# interfacez.net
KiCad netlist of a schematic drawn in EAGLE
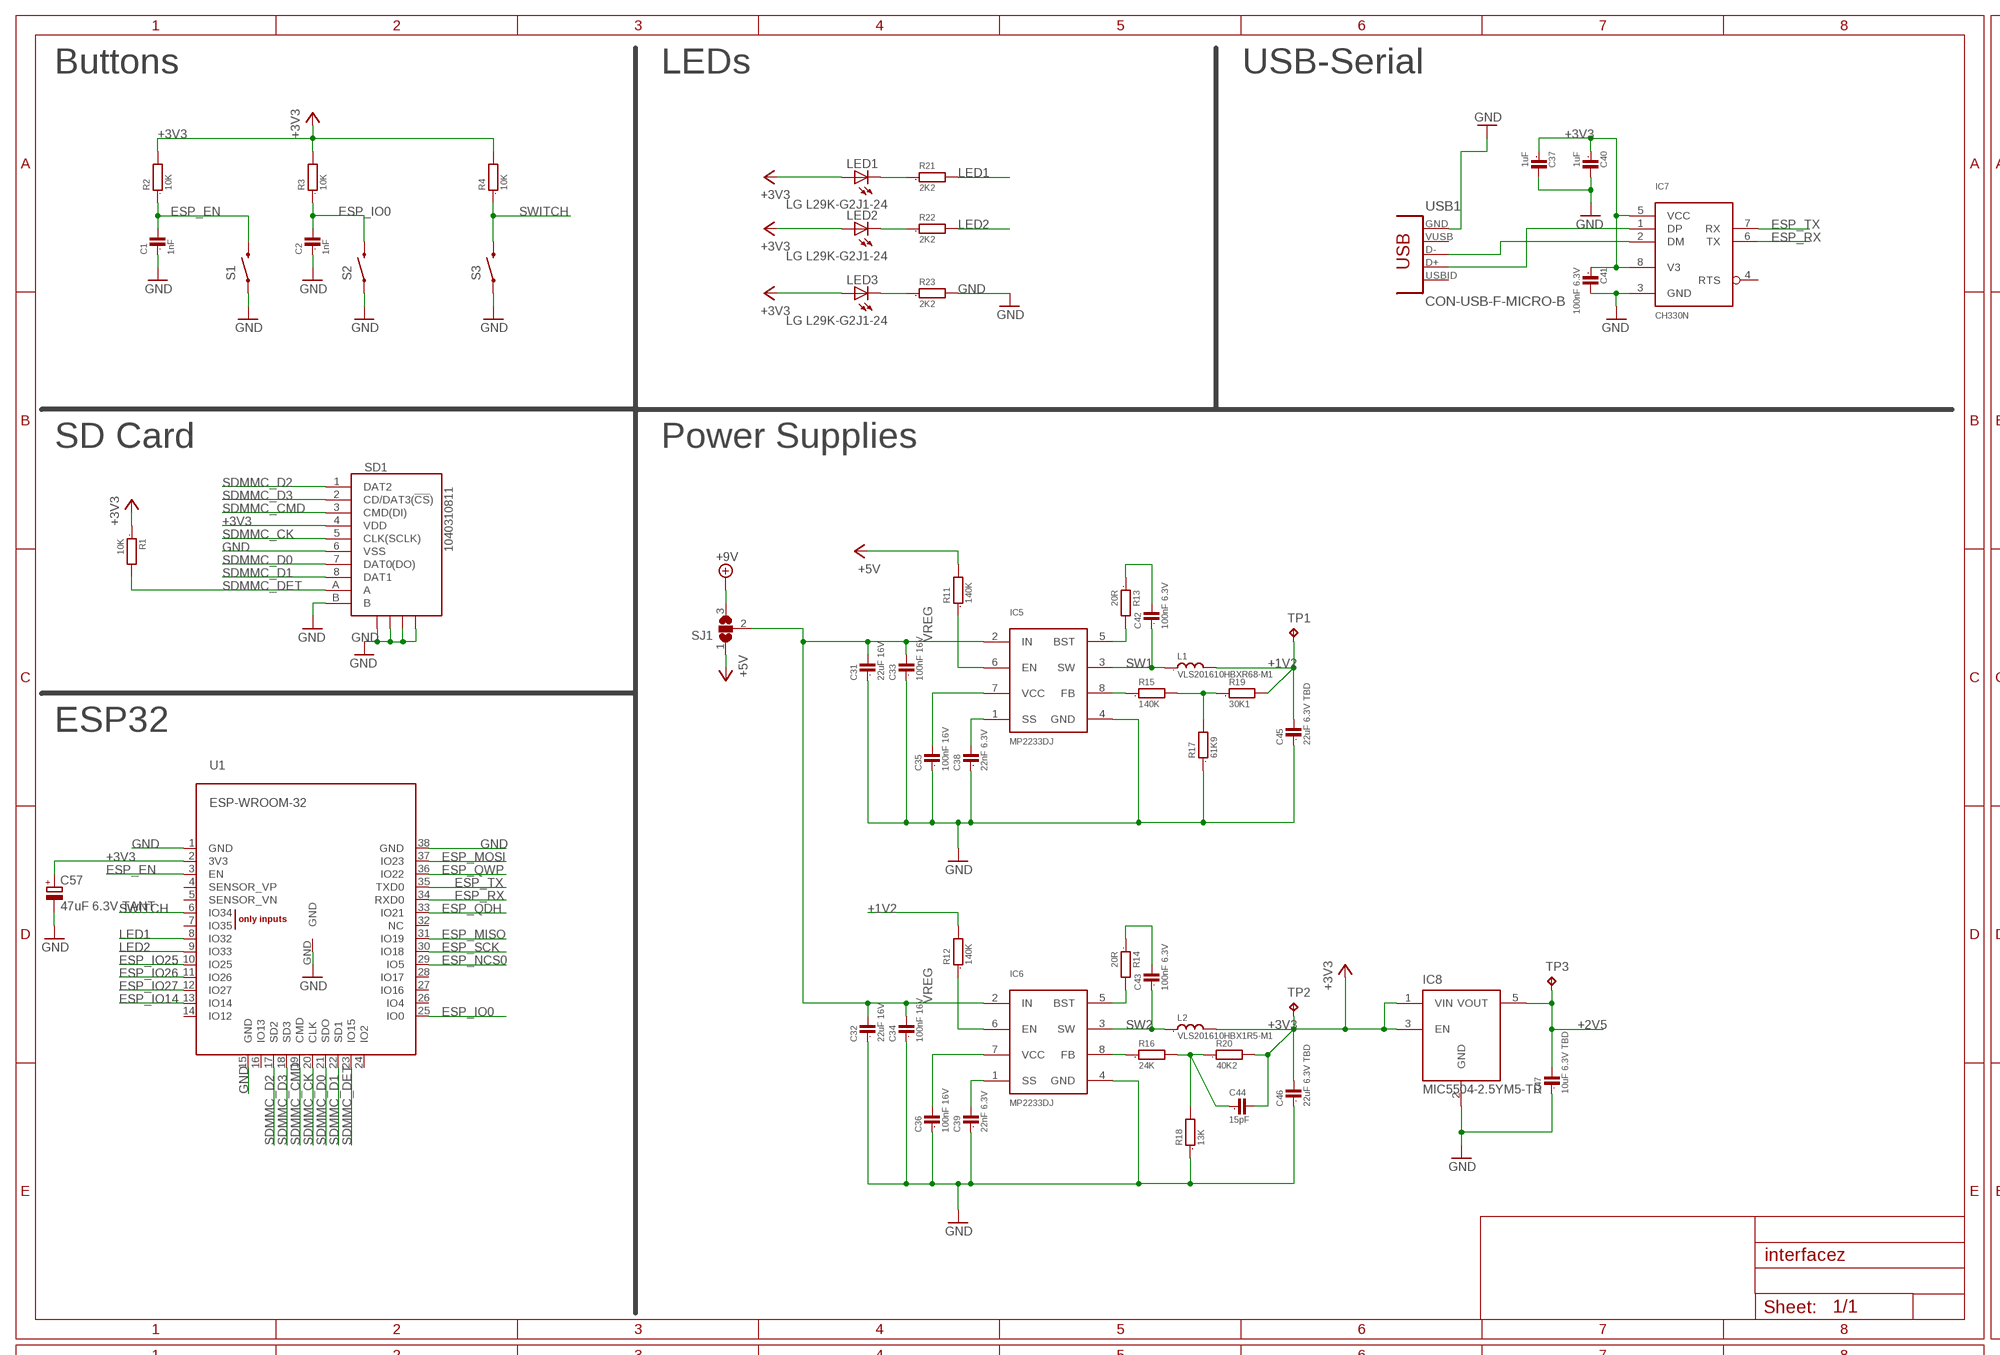
[diagram p0: schematic, sheet 1, part 1 of 3]
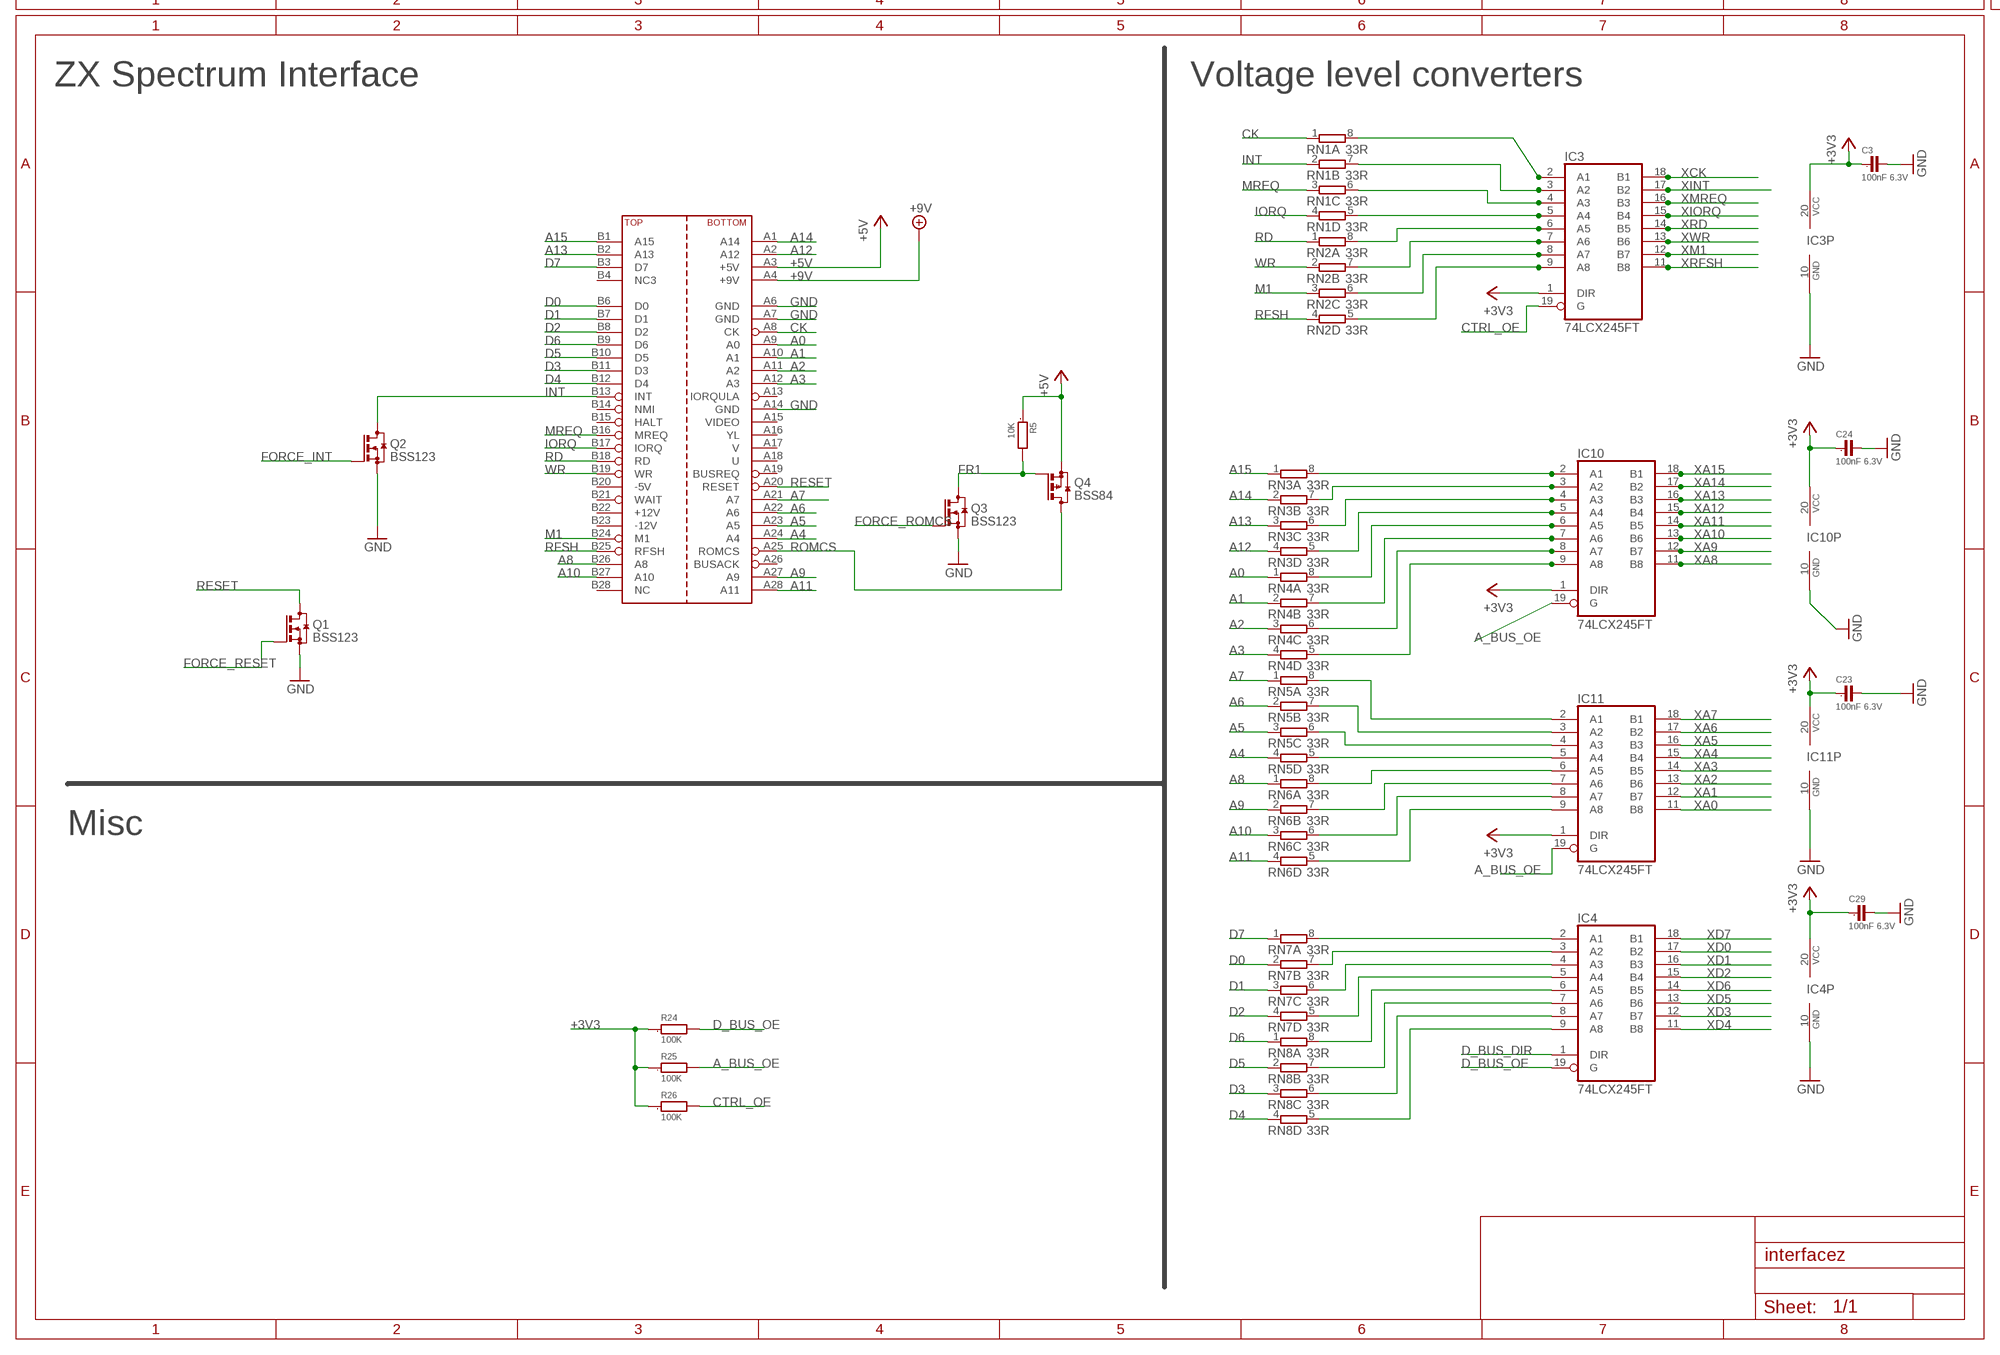
[diagram p1: schematic, sheet 1, part 2 of 3]
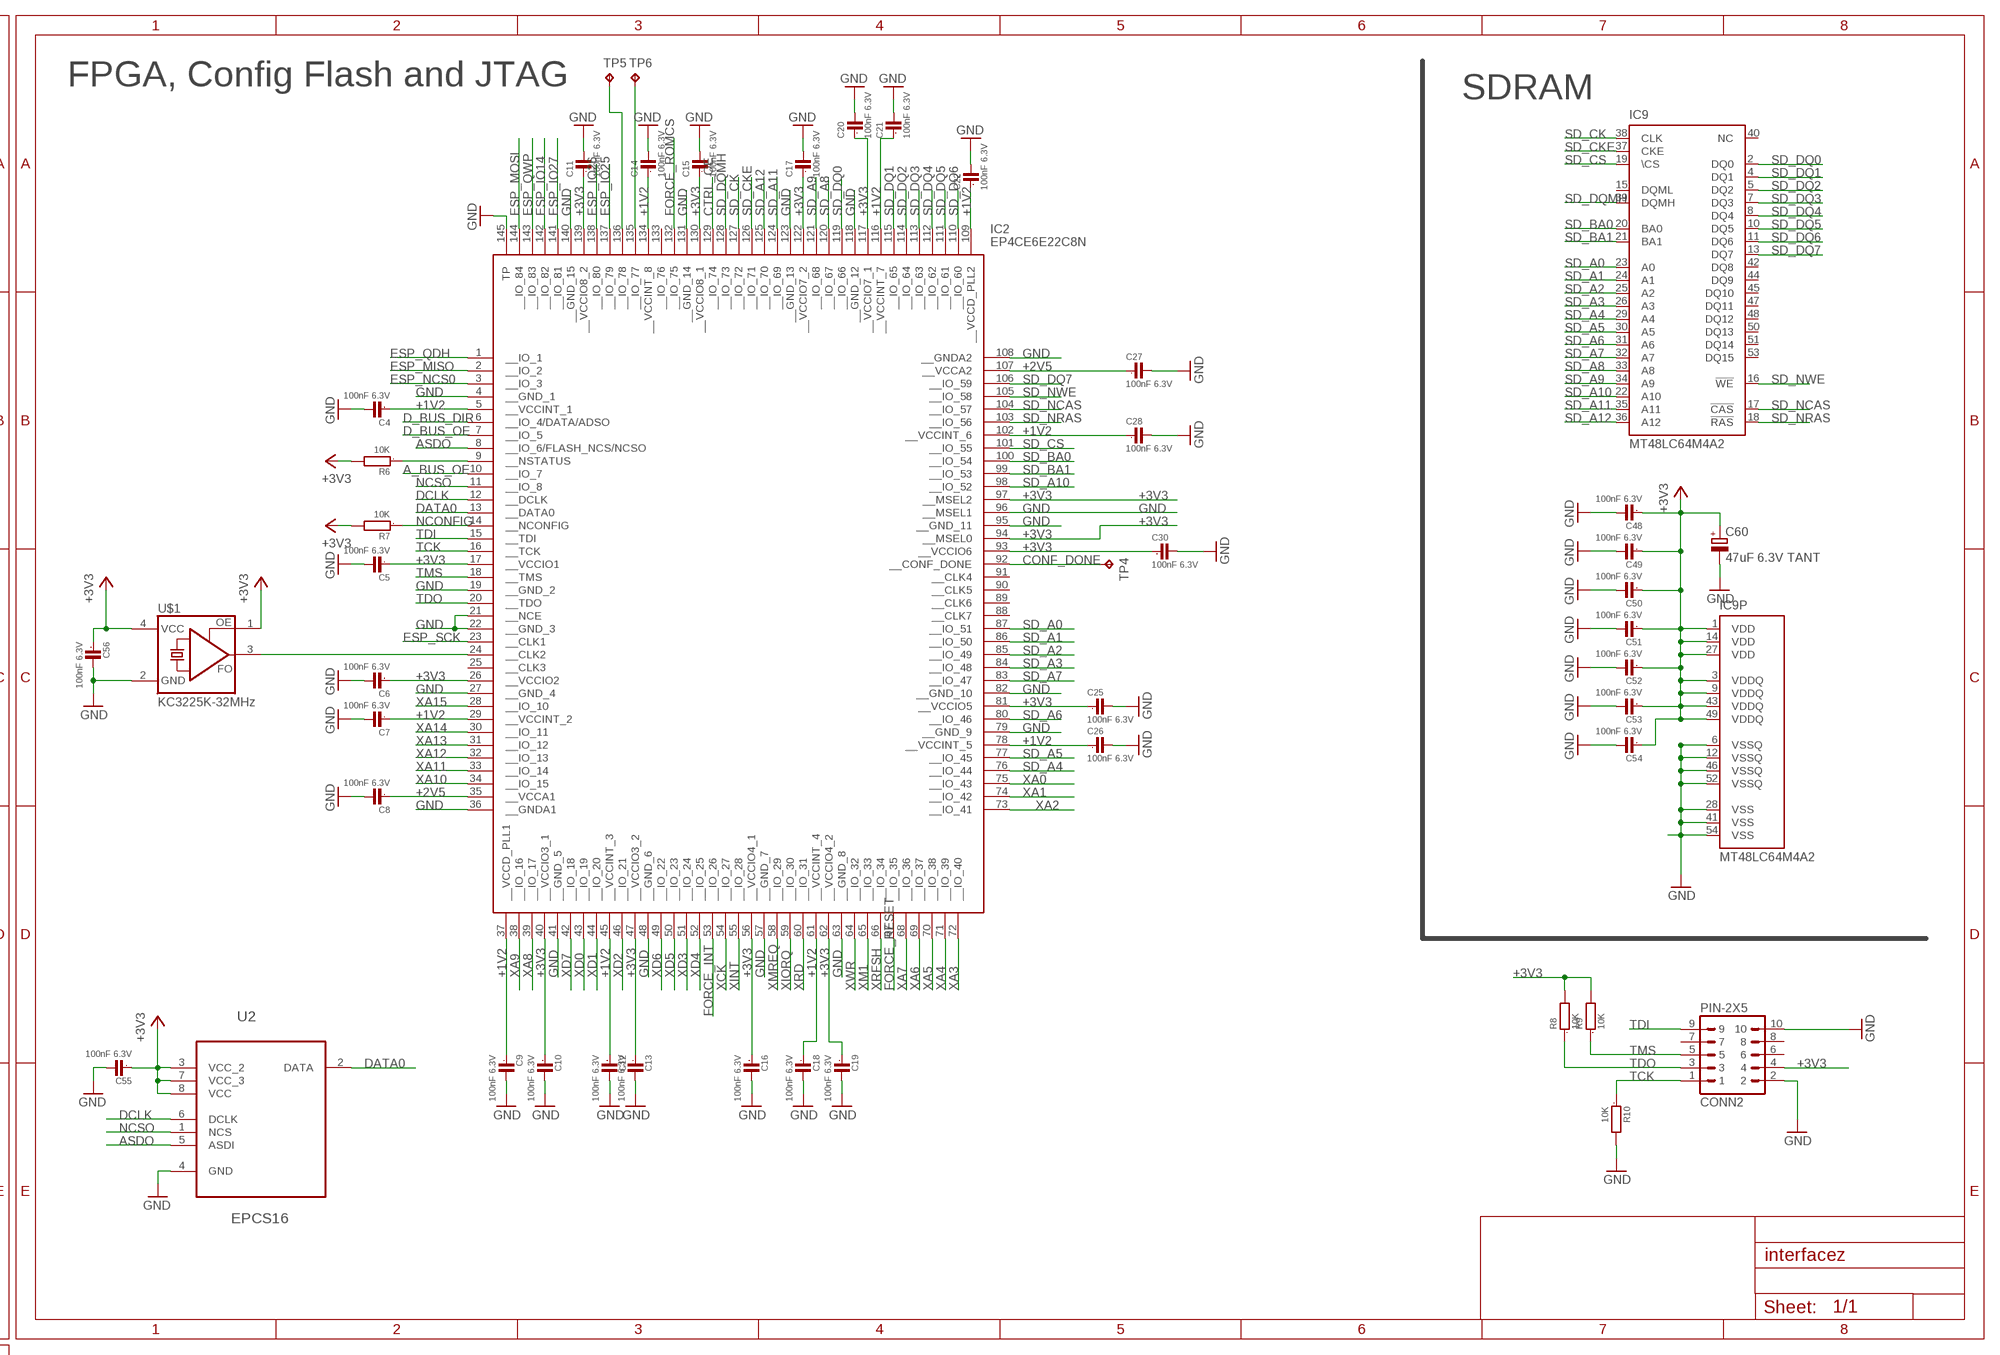
[diagram p2: schematic, sheet 1, part 3 of 3]

(export (version "E")
  (design (tool "Eeschema 10.0.6"))
  (components
    (comp (ref "C1")
      (value "1nF")
      (footprint "eagle-import:0603")
      (libsource (lib "eagle-import") (part "C0603"))
    )
    (comp (ref "C2")
      (value "1nF")
      (footprint "eagle-import:0603")
      (libsource (lib "eagle-import") (part "C0603"))
    )
    (comp (ref "C3")
      (value "100nF 6.3V")
      (footprint "eagle-import:0603")
      (libsource (lib "eagle-import") (part "C0603"))
    )
    (comp (ref "C4")
      (value "100nF 6.3V")
      (footprint "eagle-import:0603")
      (libsource (lib "eagle-import") (part "C0603"))
    )
    (comp (ref "C5")
      (value "100nF 6.3V")
      (footprint "eagle-import:0603")
      (libsource (lib "eagle-import") (part "C0603"))
    )
    (comp (ref "C6")
      (value "100nF 6.3V")
      (footprint "eagle-import:0603")
      (libsource (lib "eagle-import") (part "C0603"))
    )
    (comp (ref "C7")
      (value "100nF 6.3V")
      (footprint "eagle-import:0603")
      (libsource (lib "eagle-import") (part "C0603"))
    )
    (comp (ref "C8")
      (value "100nF 6.3V")
      (footprint "eagle-import:0603")
      (libsource (lib "eagle-import") (part "C0603"))
    )
    (comp (ref "C9")
      (value "100nF 6.3V")
      (footprint "eagle-import:0603")
      (libsource (lib "eagle-import") (part "C0603"))
    )
    (comp (ref "C10")
      (value "100nF 6.3V")
      (footprint "eagle-import:0603")
      (libsource (lib "eagle-import") (part "C0603"))
    )
    (comp (ref "C11")
      (value "100nF 6.3V")
      (footprint "eagle-import:0603")
      (libsource (lib "eagle-import") (part "C0603"))
    )
    (comp (ref "C12")
      (value "100nF 6.3V")
      (footprint "eagle-import:0603")
      (libsource (lib "eagle-import") (part "C0603"))
    )
    (comp (ref "C13")
      (value "100nF 6.3V")
      (footprint "eagle-import:0603")
      (libsource (lib "eagle-import") (part "C0603"))
    )
    (comp (ref "C14")
      (value "100nF 6.3V")
      (footprint "eagle-import:0603")
      (libsource (lib "eagle-import") (part "C0603"))
    )
    (comp (ref "C15")
      (value "100nF 6.3V")
      (footprint "eagle-import:0603")
      (libsource (lib "eagle-import") (part "C0603"))
    )
    (comp (ref "C16")
      (value "100nF 6.3V")
      (footprint "eagle-import:0603")
      (libsource (lib "eagle-import") (part "C0603"))
    )
    (comp (ref "C17")
      (value "100nF 6.3V")
      (footprint "eagle-import:0603")
      (libsource (lib "eagle-import") (part "C0603"))
    )
    (comp (ref "C18")
      (value "100nF 6.3V")
      (footprint "eagle-import:0603")
      (libsource (lib "eagle-import") (part "C0603"))
    )
    (comp (ref "C19")
      (value "100nF 6.3V")
      (footprint "eagle-import:0603")
      (libsource (lib "eagle-import") (part "C0603"))
    )
    (comp (ref "C20")
      (value "100nF 6.3V")
      (footprint "eagle-import:0603")
      (libsource (lib "eagle-import") (part "C0603"))
    )
    (comp (ref "C21")
      (value "100nF 6.3V")
      (footprint "eagle-import:0603")
      (libsource (lib "eagle-import") (part "C0603"))
    )
    (comp (ref "C22")
      (value "100nF 6.3V")
      (footprint "eagle-import:0603")
      (libsource (lib "eagle-import") (part "C0603"))
    )
    (comp (ref "C23")
      (value "100nF 6.3V")
      (footprint "eagle-import:0603")
      (libsource (lib "eagle-import") (part "C0603"))
    )
    (comp (ref "C24")
      (value "100nF 6.3V")
      (footprint "eagle-import:0603")
      (libsource (lib "eagle-import") (part "C0603"))
    )
    (comp (ref "C25")
      (value "100nF 6.3V")
      (footprint "eagle-import:0603")
      (libsource (lib "eagle-import") (part "C0603"))
    )
    (comp (ref "C26")
      (value "100nF 6.3V")
      (footprint "eagle-import:0603")
      (libsource (lib "eagle-import") (part "C0603"))
    )
    (comp (ref "C27")
      (value "100nF 6.3V")
      (footprint "eagle-import:0603")
      (libsource (lib "eagle-import") (part "C0603"))
    )
    (comp (ref "C28")
      (value "100nF 6.3V")
      (footprint "eagle-import:0603")
      (libsource (lib "eagle-import") (part "C0603"))
    )
    (comp (ref "C29")
      (value "100nF 6.3V")
      (footprint "eagle-import:0603")
      (libsource (lib "eagle-import") (part "C0603"))
    )
    (comp (ref "C30")
      (value "100nF 6.3V")
      (footprint "eagle-import:0603")
      (libsource (lib "eagle-import") (part "C0603"))
    )
    (comp (ref "C31")
      (value "22uF 16V")
      (footprint "eagle-import:1210")
      (libsource (lib "eagle-import") (part "C1210"))
    )
    (comp (ref "C32")
      (value "22uF 16V")
      (footprint "eagle-import:1210")
      (libsource (lib "eagle-import") (part "C1210"))
    )
    (comp (ref "C33")
      (value "100nF 16V")
      (footprint "eagle-import:0603")
      (libsource (lib "eagle-import") (part "C0603"))
    )
    (comp (ref "C34")
      (value "100nF 16V")
      (footprint "eagle-import:0603")
      (libsource (lib "eagle-import") (part "C0603"))
    )
    (comp (ref "C35")
      (value "100nF 16V")
      (footprint "eagle-import:0603")
      (libsource (lib "eagle-import") (part "C0603"))
    )
    (comp (ref "C36")
      (value "100nF 16V")
      (footprint "eagle-import:0603")
      (libsource (lib "eagle-import") (part "C0603"))
    )
    (comp (ref "C37")
      (value "1uF")
      (footprint "eagle-import:0603")
      (libsource (lib "eagle-import") (part "C0603"))
    )
    (comp (ref "C38")
      (value "22nF 6.3V")
      (footprint "eagle-import:0603")
      (libsource (lib "eagle-import") (part "C0603"))
    )
    (comp (ref "C39")
      (value "22nF 6.3V")
      (footprint "eagle-import:0603")
      (libsource (lib "eagle-import") (part "C0603"))
    )
    (comp (ref "C40")
      (value "1uF")
      (footprint "eagle-import:0603")
      (libsource (lib "eagle-import") (part "C0603"))
    )
    (comp (ref "C41")
      (value "100nF 6.3V")
      (footprint "eagle-import:0603")
      (libsource (lib "eagle-import") (part "C0603"))
    )
    (comp (ref "C42")
      (value "100nF 6.3V")
      (footprint "eagle-import:0603")
      (libsource (lib "eagle-import") (part "C0603"))
    )
    (comp (ref "C43")
      (value "100nF 6.3V")
      (footprint "eagle-import:0603")
      (libsource (lib "eagle-import") (part "C0603"))
    )
    (comp (ref "C44")
      (value "15pF")
      (footprint "eagle-import:0603")
      (libsource (lib "eagle-import") (part "C0603"))
    )
    (comp (ref "C45")
      (value "22uF 6.3V TBD")
      (footprint "eagle-import:0805")
      (libsource (lib "eagle-import") (part "C0805"))
    )
    (comp (ref "C46")
      (value "22uF 6.3V TBD")
      (footprint "eagle-import:0805")
      (libsource (lib "eagle-import") (part "C0805"))
    )
    (comp (ref "C47")
      (value "10uF 6.3V TBD")
      (footprint "eagle-import:0805")
      (libsource (lib "eagle-import") (part "C0805"))
    )
    (comp (ref "C48")
      (value "100nF 6.3V")
      (footprint "eagle-import:0603")
      (libsource (lib "eagle-import") (part "C0603"))
    )
    (comp (ref "C49")
      (value "100nF 6.3V")
      (footprint "eagle-import:0603")
      (libsource (lib "eagle-import") (part "C0603"))
    )
    (comp (ref "C50")
      (value "100nF 6.3V")
      (footprint "eagle-import:0603")
      (libsource (lib "eagle-import") (part "C0603"))
    )
    (comp (ref "C51")
      (value "100nF 6.3V")
      (footprint "eagle-import:0603")
      (libsource (lib "eagle-import") (part "C0603"))
    )
    (comp (ref "C52")
      (value "100nF 6.3V")
      (footprint "eagle-import:0603")
      (libsource (lib "eagle-import") (part "C0603"))
    )
    (comp (ref "C53")
      (value "100nF 6.3V")
      (footprint "eagle-import:0603")
      (libsource (lib "eagle-import") (part "C0603"))
    )
    (comp (ref "C54")
      (value "100nF 6.3V")
      (footprint "eagle-import:0603")
      (libsource (lib "eagle-import") (part "C0603"))
    )
    (comp (ref "C55")
      (value "100nF 6.3V")
      (footprint "eagle-import:0603")
      (libsource (lib "eagle-import") (part "C0603"))
    )
    (comp (ref "C56")
      (value "100nF 6.3V")
      (footprint "eagle-import:0603")
      (libsource (lib "eagle-import") (part "C0603"))
    )
    (comp (ref "C57")
      (value "47uF 6.3V TANT")
      (footprint "eagle-import:TANT_CASE_A")
      (libsource (lib "eagle-import") (part "TANT_CASE_A"))
    )
    (comp (ref "C60")
      (value "47uF 6.3V TANT")
      (footprint "eagle-import:TANT_CASE_A")
      (libsource (lib "eagle-import") (part "TANT_CASE_A"))
    )
    (comp (ref "CONN1")
      (value "ZX_EDGE_DAUGHTERBOARD")
      (footprint "eagle-import:ZX-EDGE-DAUGHTERBOARD")
      (libsource (lib "eagle-import") (part "ZX_EDGE_DAUGHTERBOARD"))
    )
    (comp (ref "CONN2")
      (value "PIN-2X5")
      (footprint "eagle-import:PIN-2X5")
      (libsource (lib "eagle-import") (part "PIN-2X5"))
    )
    (comp (ref "IC2")
      (value "EP4CE6E22C8N")
      (footprint "eagle-import:QFP50P2200X2200X165-145N")
      (fields (field (name "MOUSER_PART_NUMBER") "989-EP4CE6E22C8N"))
      (libsource (lib "eagle-import") (part "EP4CE6E22C8N"))
    )
    (comp (ref "IC3")
      (value "74LCX245FT")
      (footprint "eagle-import:TSSOP20")
      (libsource (lib "eagle-import") (part "74245"))
    )
    (comp (ref "IC4")
      (value "74LCX245FT")
      (footprint "eagle-import:TSSOP20")
      (libsource (lib "eagle-import") (part "74245"))
    )
    (comp (ref "IC5")
      (value "MP2233DJ")
      (footprint "eagle-import:SOT23-8L")
      (libsource (lib "eagle-import") (part "MP2233DJ"))
    )
    (comp (ref "IC6")
      (value "MP2233DJ")
      (footprint "eagle-import:SOT23-8L")
      (libsource (lib "eagle-import") (part "MP2233DJ"))
    )
    (comp (ref "IC7")
      (value "CH330N")
      (footprint "eagle-import:SOIC8")
      (libsource (lib "eagle-import") (part "CH330N"))
    )
    (comp (ref "IC8")
      (value "MIC5504-2.5YM5-TR")
      (footprint "eagle-import:SOT23-5L")
      (libsource (lib "eagle-import") (part "MIC550X"))
    )
    (comp (ref "IC9")
      (value "MT48LC64M4A2")
      (footprint "eagle-import:TSOP54-400")
      (libsource (lib "eagle-import") (part "MT48LC64M4A2"))
    )
    (comp (ref "IC10")
      (value "74LCX245FT")
      (footprint "eagle-import:TSSOP20")
      (libsource (lib "eagle-import") (part "74245"))
    )
    (comp (ref "IC11")
      (value "74LCX245FT")
      (footprint "eagle-import:TSSOP20")
      (libsource (lib "eagle-import") (part "74245"))
    )
    (comp (ref "L1")
      (value "VLS201610HBXR68-M1")
      (footprint "eagle-import:IND_0806")
      (libsource (lib "eagle-import") (part "VLS201610HBXR68-M1"))
    )
    (comp (ref "L2")
      (value "VLS201610HBX1R5-M1")
      (footprint "eagle-import:IND_0806")
      (libsource (lib "eagle-import") (part "VLS201610HBX1R5-M1"))
    )
    (comp (ref "LED1")
      (value "LG L29K-G2J1-24")
      (footprint "eagle-import:LED-603")
      (libsource (lib "eagle-import") (part "LED-0603"))
    )
    (comp (ref "LED2")
      (value "LG L29K-G2J1-24")
      (footprint "eagle-import:LED-603")
      (libsource (lib "eagle-import") (part "LED-0603"))
    )
    (comp (ref "LED3")
      (value "LG L29K-G2J1-24")
      (footprint "eagle-import:LED-603")
      (libsource (lib "eagle-import") (part "LED-0603"))
    )
    (comp (ref "Q1")
      (value "BSS123")
      (footprint "eagle-import:SOT23")
      (libsource (lib "eagle-import") (part "BSS123"))
    )
    (comp (ref "Q2")
      (value "BSS123")
      (footprint "eagle-import:SOT23")
      (libsource (lib "eagle-import") (part "BSS123"))
    )
    (comp (ref "Q3")
      (value "BSS123")
      (footprint "eagle-import:SOT23")
      (libsource (lib "eagle-import") (part "BSS123"))
    )
    (comp (ref "Q4")
      (value "BSS84")
      (footprint "eagle-import:SOT23")
      (libsource (lib "eagle-import") (part "BSS84"))
    )
    (comp (ref "R1")
      (value "10K")
      (footprint "eagle-import:0603")
      (libsource (lib "eagle-import") (part "R0603"))
    )
    (comp (ref "R2")
      (value "10K")
      (footprint "eagle-import:0603")
      (libsource (lib "eagle-import") (part "R0603"))
    )
    (comp (ref "R3")
      (value "10K")
      (footprint "eagle-import:0603")
      (libsource (lib "eagle-import") (part "R0603"))
    )
    (comp (ref "R4")
      (value "10K")
      (footprint "eagle-import:0603")
      (libsource (lib "eagle-import") (part "R0603"))
    )
    (comp (ref "R5")
      (value "10K")
      (footprint "eagle-import:0603")
      (libsource (lib "eagle-import") (part "R0603"))
    )
    (comp (ref "R6")
      (value "10K")
      (footprint "eagle-import:0603")
      (libsource (lib "eagle-import") (part "R0603"))
    )
    (comp (ref "R7")
      (value "10K")
      (footprint "eagle-import:0603")
      (libsource (lib "eagle-import") (part "R0603"))
    )
    (comp (ref "R8")
      (value "10K")
      (footprint "eagle-import:0603")
      (libsource (lib "eagle-import") (part "R0603"))
    )
    (comp (ref "R9")
      (value "10K")
      (footprint "eagle-import:0603")
      (libsource (lib "eagle-import") (part "R0603"))
    )
    (comp (ref "R10")
      (value "10K")
      (footprint "eagle-import:0603")
      (libsource (lib "eagle-import") (part "R0603"))
    )
    (comp (ref "R11")
      (value "140K")
      (footprint "eagle-import:0603")
      (libsource (lib "eagle-import") (part "R0603"))
    )
    (comp (ref "R12")
      (value "140K")
      (footprint "eagle-import:0603")
      (libsource (lib "eagle-import") (part "R0603"))
    )
    (comp (ref "R13")
      (value "20R")
      (footprint "eagle-import:0603")
      (libsource (lib "eagle-import") (part "R0603"))
    )
    (comp (ref "R14")
      (value "20R")
      (footprint "eagle-import:0603")
      (libsource (lib "eagle-import") (part "R0603"))
    )
    (comp (ref "R15")
      (value "140K")
      (footprint "eagle-import:0603")
      (libsource (lib "eagle-import") (part "R0603"))
    )
    (comp (ref "R16")
      (value "24K")
      (footprint "eagle-import:0603")
      (libsource (lib "eagle-import") (part "R0603"))
    )
    (comp (ref "R17")
      (value "61K9")
      (footprint "eagle-import:0603")
      (libsource (lib "eagle-import") (part "R0603"))
    )
    (comp (ref "R18")
      (value "13K")
      (footprint "eagle-import:0603")
      (libsource (lib "eagle-import") (part "R0603"))
    )
    (comp (ref "R19")
      (value "30K1")
      (footprint "eagle-import:0603")
      (libsource (lib "eagle-import") (part "R0603"))
    )
    (comp (ref "R20")
      (value "40K2")
      (footprint "eagle-import:0603")
      (libsource (lib "eagle-import") (part "R0603"))
    )
    (comp (ref "R21")
      (value "2K2")
      (footprint "eagle-import:0603")
      (libsource (lib "eagle-import") (part "R0603"))
    )
    (comp (ref "R22")
      (value "2K2")
      (footprint "eagle-import:0603")
      (libsource (lib "eagle-import") (part "R0603"))
    )
    (comp (ref "R23")
      (value "2K2")
      (footprint "eagle-import:0603")
      (libsource (lib "eagle-import") (part "R0603"))
    )
    (comp (ref "R24")
      (value "100K")
      (footprint "eagle-import:0603")
      (libsource (lib "eagle-import") (part "R0603"))
    )
    (comp (ref "R25")
      (value "100K")
      (footprint "eagle-import:0603")
      (libsource (lib "eagle-import") (part "R0603"))
    )
    (comp (ref "R26")
      (value "100K")
      (footprint "eagle-import:0603")
      (libsource (lib "eagle-import") (part "R0603"))
    )
    (comp (ref "RN1")
      (value "33R")
      (footprint "eagle-import:EXB28V")
      (libsource (lib "eagle-import") (part "4R-NEXB28V"))
    )
    (comp (ref "RN2")
      (value "33R")
      (footprint "eagle-import:EXB28V")
      (libsource (lib "eagle-import") (part "4R-NEXB28V"))
    )
    (comp (ref "RN3")
      (value "33R")
      (footprint "eagle-import:EXB28V")
      (libsource (lib "eagle-import") (part "4R-NEXB28V"))
    )
    (comp (ref "RN4")
      (value "33R")
      (footprint "eagle-import:EXB28V")
      (libsource (lib "eagle-import") (part "4R-NEXB28V"))
    )
    (comp (ref "RN5")
      (value "33R")
      (footprint "eagle-import:EXB28V")
      (libsource (lib "eagle-import") (part "4R-NEXB28V"))
    )
    (comp (ref "RN6")
      (value "33R")
      (footprint "eagle-import:EXB28V")
      (libsource (lib "eagle-import") (part "4R-NEXB28V"))
    )
    (comp (ref "RN7")
      (value "33R")
      (footprint "eagle-import:EXB28V")
      (libsource (lib "eagle-import") (part "4R-NEXB28V"))
    )
    (comp (ref "RN8")
      (value "33R")
      (footprint "eagle-import:EXB28V")
      (libsource (lib "eagle-import") (part "4R-NEXB28V"))
    )
    (comp (ref "S1")
      (value "SWITCHES_SMD-4")
      (footprint "eagle-import:TACTILE_SWITCH_TALL")
      (libsource (lib "eagle-import") (part "SWITCHES_SMD-4"))
    )
    (comp (ref "S2")
      (value "SWITCHES_SMD-4")
      (footprint "eagle-import:TACTILE_SWITCH_TALL")
      (libsource (lib "eagle-import") (part "SWITCHES_SMD-4"))
    )
    (comp (ref "S3")
      (value "SWITCHES_SMD-4")
      (footprint "eagle-import:TACTILE_SWITCH_TALL")
      (libsource (lib "eagle-import") (part "SWITCHES_SMD-4"))
    )
    (comp (ref "SD1")
      (value "1040310811")
      (footprint "eagle-import:1040310811")
      (libsource (lib "eagle-import") (part "1040310811"))
    )
    (comp (ref "SJ1")
      (value "SJ2W")
      (footprint "eagle-import:SJ_2")
      (libsource (lib "eagle-import") (part "SJ2W"))
    )
    (comp (ref "TP1")
      (value "TPTP12R")
      (footprint "eagle-import:TP12R")
      (libsource (lib "eagle-import") (part "TPTP12R"))
    )
    (comp (ref "TP2")
      (value "TPTP12R")
      (footprint "eagle-import:TP12R")
      (libsource (lib "eagle-import") (part "TPTP12R"))
    )
    (comp (ref "TP3")
      (value "TPTP12R")
      (footprint "eagle-import:TP12R")
      (libsource (lib "eagle-import") (part "TPTP12R"))
    )
    (comp (ref "TP4")
      (value "TPTP08R")
      (footprint "eagle-import:TP08R")
      (libsource (lib "eagle-import") (part "TPTP08R"))
    )
    (comp (ref "TP5")
      (value "TPTP12R")
      (footprint "eagle-import:TP12R")
      (libsource (lib "eagle-import") (part "TPTP12R"))
    )
    (comp (ref "TP6")
      (value "TPTP12R")
      (footprint "eagle-import:TP12R")
      (libsource (lib "eagle-import") (part "TPTP12R"))
    )
    (comp (ref "U$1")
      (value "KC3225K-32MHz")
      (footprint "eagle-import:KC3225K")
      (libsource (lib "eagle-import") (part "KC3225K"))
    )
    (comp (ref "U1")
      (value "ESP-WROOM-32")
      (footprint "eagle-import:ESP-WROOM-32")
      (libsource (lib "eagle-import") (part "ESP-WROOM-32"))
    )
    (comp (ref "U2")
      (value "EPCS16")
      (footprint "eagle-import:SOIC127P600X175-8N")
      (fields (field (name "MPN") "EPCS1SI8N"))
      (libsource (lib "eagle-import") (part "EPCS1SI8N"))
    )
    (comp (ref "USB1")
      (value "CON-USB-F-MICRO-B")
      (footprint "eagle-import:CONN_USB_MICRO-B")
      (libsource (lib "eagle-import") (part "CON-USB-F-MICRO-B"))
    )
  )
  (nets
    (net (code "1") (name "+3V3") (class "Default")
      (node (ref "C10") (pin "1") (pinfunction "1_1") (pintype "passive"))
      (node (ref "C11") (pin "1") (pinfunction "1_1") (pintype "passive"))
      (node (ref "C13") (pin "1") (pinfunction "1_1") (pintype "passive"))
      (node (ref "C15") (pin "1") (pinfunction "1_1") (pintype "passive"))
      (node (ref "C16") (pin "1") (pinfunction "1_1") (pintype "passive"))
      (node (ref "C17") (pin "1") (pinfunction "1_1") (pintype "passive"))
      (node (ref "C19") (pin "1") (pinfunction "1_1") (pintype "passive"))
      (node (ref "C20") (pin "1") (pinfunction "1_1") (pintype "passive"))
      (node (ref "C23") (pin "1") (pinfunction "1_1") (pintype "passive"))
      (node (ref "C24") (pin "1") (pinfunction "1_1") (pintype "passive"))
      (node (ref "C25") (pin "1") (pinfunction "1_1") (pintype "passive"))
      (node (ref "C29") (pin "1") (pinfunction "1_1") (pintype "passive"))
      (node (ref "C3") (pin "1") (pinfunction "1_1") (pintype "passive"))
      (node (ref "C30") (pin "1") (pinfunction "1_1") (pintype "passive"))
      (node (ref "C37") (pin "1") (pinfunction "1_1") (pintype "passive"))
      (node (ref "C40") (pin "1") (pinfunction "1_1") (pintype "passive"))
      (node (ref "C41") (pin "1") (pinfunction "1_1") (pintype "passive"))
      (node (ref "C44") (pin "2") (pinfunction "2_2") (pintype "passive"))
      (node (ref "C46") (pin "2") (pinfunction "2_2") (pintype "passive"))
      (node (ref "C48") (pin "1") (pinfunction "1_1") (pintype "passive"))
      (node (ref "C49") (pin "1") (pinfunction "1_1") (pintype "passive"))
      (node (ref "C5") (pin "1") (pinfunction "1_1") (pintype "passive"))
      (node (ref "C50") (pin "1") (pinfunction "1_1") (pintype "passive"))
      (node (ref "C51") (pin "1") (pinfunction "1_1") (pintype "passive"))
      (node (ref "C52") (pin "1") (pinfunction "1_1") (pintype "passive"))
      (node (ref "C53") (pin "1") (pinfunction "1_1") (pintype "passive"))
      (node (ref "C54") (pin "1") (pinfunction "1_1") (pintype "passive"))
      (node (ref "C55") (pin "1") (pinfunction "1_1") (pintype "passive"))
      (node (ref "C56") (pin "1") (pinfunction "1_1") (pintype "passive"))
      (node (ref "C57") (pin "PLUS") (pinfunction "+_PLUS") (pintype "passive"))
      (node (ref "C6") (pin "1") (pinfunction "1_1") (pintype "passive"))
      (node (ref "C60") (pin "PLUS") (pinfunction "+_PLUS") (pintype "passive"))
      (node (ref "CONN2") (pin "4") (pinfunction "4_4") (pintype "passive"))
      (node (ref "IC10") (pin "1") (pinfunction "DIR_1") (pintype "input"))
      (node (ref "IC10") (pin "20") (pinfunction "VCC_20") (pintype "power_in"))
      (node (ref "IC11") (pin "1") (pinfunction "DIR_1") (pintype "input"))
      (node (ref "IC11") (pin "20") (pinfunction "VCC_20") (pintype "power_in"))
      (node (ref "IC2") (pin "117") (pinfunction "__VCCIO7_1_117") (pintype "power_in"))
      (node (ref "IC2") (pin "122") (pinfunction "__VCCIO7_2_122") (pintype "power_in"))
      (node (ref "IC2") (pin "130") (pinfunction "__VCCIO8_1_130") (pintype "power_in"))
      (node (ref "IC2") (pin "139") (pinfunction "__VCCIO8_2_139") (pintype "power_in"))
      (node (ref "IC2") (pin "17") (pinfunction "__VCCIO1_17") (pintype "power_in"))
      (node (ref "IC2") (pin "26") (pinfunction "__VCCIO2_26") (pintype "power_in"))
      (node (ref "IC2") (pin "40") (pinfunction "__VCCIO3_1_40") (pintype "power_in"))
      (node (ref "IC2") (pin "47") (pinfunction "__VCCIO3_2_47") (pintype "power_in"))
      (node (ref "IC2") (pin "56") (pinfunction "__VCCIO4_1_56") (pintype "power_in"))
      (node (ref "IC2") (pin "62") (pinfunction "__VCCIO4_2_62") (pintype "power_in"))
      (node (ref "IC2") (pin "81") (pinfunction "__VCCIO5_81") (pintype "power_in"))
      (node (ref "IC2") (pin "93") (pinfunction "__VCCIO6_93") (pintype "power_in"))
      (node (ref "IC2") (pin "94") (pinfunction "__MSEL0_94") (pintype "bidirectional"))
      (node (ref "IC2") (pin "97") (pinfunction "__MSEL2_97") (pintype "bidirectional"))
      (node (ref "IC3") (pin "1") (pinfunction "DIR_1") (pintype "input"))
      (node (ref "IC3") (pin "20") (pinfunction "VCC_20") (pintype "power_in"))
      (node (ref "IC4") (pin "20") (pinfunction "VCC_20") (pintype "power_in"))
      (node (ref "IC7") (pin "5") (pinfunction "VCC_5") (pintype "power_in"))
      (node (ref "IC7") (pin "8") (pinfunction "V3_8") (pintype "passive"))
      (node (ref "IC8") (pin "1") (pinfunction "VIN_1") (pintype "power_in"))
      (node (ref "IC8") (pin "3") (pinfunction "EN_3") (pintype "input"))
      (node (ref "IC9") (pin "1") (pinfunction "VDD_1") (pintype "power_in"))
      (node (ref "IC9") (pin "14") (pinfunction "VDD_14") (pintype "power_in"))
      (node (ref "IC9") (pin "27") (pinfunction "VDD_27") (pintype "power_in"))
      (node (ref "IC9") (pin "3") (pinfunction "VDDQ_3") (pintype "power_in"))
      (node (ref "IC9") (pin "43") (pinfunction "VDDQ_43") (pintype "power_in"))
      (node (ref "IC9") (pin "49") (pinfunction "VDDQ_49") (pintype "power_in"))
      (node (ref "IC9") (pin "9") (pinfunction "VDDQ_9") (pintype "power_in"))
      (node (ref "L2") (pin "P$2") (pinfunction "2_P$2") (pintype "passive"))
      (node (ref "LED1") (pin "A") (pinfunction "A_A") (pintype "passive"))
      (node (ref "LED2") (pin "A") (pinfunction "A_A") (pintype "passive"))
      (node (ref "LED3") (pin "A") (pinfunction "A_A") (pintype "passive"))
      (node (ref "R1") (pin "1") (pinfunction "1_1") (pintype "passive"))
      (node (ref "R2") (pin "2") (pinfunction "2_2") (pintype "passive"))
      (node (ref "R20") (pin "2") (pinfunction "2_2") (pintype "passive"))
      (node (ref "R24") (pin "1") (pinfunction "1_1") (pintype "passive"))
      (node (ref "R25") (pin "1") (pinfunction "1_1") (pintype "passive"))
      (node (ref "R26") (pin "1") (pinfunction "1_1") (pintype "passive"))
      (node (ref "R3") (pin "2") (pinfunction "2_2") (pintype "passive"))
      (node (ref "R4") (pin "2") (pinfunction "2_2") (pintype "passive"))
      (node (ref "R6") (pin "2") (pinfunction "2_2") (pintype "passive"))
      (node (ref "R7") (pin "2") (pinfunction "2_2") (pintype "passive"))
      (node (ref "R8") (pin "2") (pinfunction "2_2") (pintype "passive"))
      (node (ref "R9") (pin "2") (pinfunction "2_2") (pintype "passive"))
      (node (ref "SD1") (pin "4") (pinfunction "VDD_4") (pintype "power_in"))
      (node (ref "TP2") (pin "TP") (pinfunction "TP_TP") (pintype "input"))
      (node (ref "U$1") (pin "1") (pinfunction "OE_1") (pintype "input"))
      (node (ref "U$1") (pin "4") (pinfunction "VCC_4") (pintype "power_in"))
      (node (ref "U1") (pin "2") (pinfunction "3V3_2") (pintype "bidirectional"))
      (node (ref "U2") (pin "3") (pinfunction "VCC_2_3") (pintype "power_in"))
      (node (ref "U2") (pin "7") (pinfunction "VCC_3_7") (pintype "power_in"))
      (node (ref "U2") (pin "8") (pinfunction "VCC_8") (pintype "power_in"))
    )
    (net (code "2") (name "+5V") (class "Default")
      (node (ref "CONN1") (pin "A3") (pinfunction "+5V_A3") (pintype "power_in"))
      (node (ref "Q4") (pin "2") (pinfunction "S_2") (pintype "passive"))
      (node (ref "R11") (pin "2") (pinfunction "2_2") (pintype "passive"))
      (node (ref "R5") (pin "1") (pinfunction "1_1") (pintype "passive"))
      (node (ref "SJ1") (pin "1") (pinfunction "1_1") (pintype "passive"))
    )
    (net (code "3") (name "+9V") (class "Default")
      (node (ref "CONN1") (pin "A4") (pinfunction "+9V_A4") (pintype "power_in"))
      (node (ref "SJ1") (pin "3") (pinfunction "3_3") (pintype "passive"))
    )
    (net (code "4") (name "/+1V2") (class "Default")
      (node (ref "C12") (pin "1") (pinfunction "1_1") (pintype "passive"))
      (node (ref "C14") (pin "1") (pinfunction "1_1") (pintype "passive"))
      (node (ref "C18") (pin "1") (pinfunction "1_1") (pintype "passive"))
      (node (ref "C21") (pin "1") (pinfunction "1_1") (pintype "passive"))
      (node (ref "C22") (pin "1") (pinfunction "1_1") (pintype "passive"))
      (node (ref "C26") (pin "1") (pinfunction "1_1") (pintype "passive"))
      (node (ref "C28") (pin "1") (pinfunction "1_1") (pintype "passive"))
      (node (ref "C4") (pin "1") (pinfunction "1_1") (pintype "passive"))
      (node (ref "C45") (pin "2") (pinfunction "2_2") (pintype "passive"))
      (node (ref "C7") (pin "1") (pinfunction "1_1") (pintype "passive"))
      (node (ref "C9") (pin "1") (pinfunction "1_1") (pintype "passive"))
      (node (ref "IC2") (pin "102") (pinfunction "__VCCINT_6_102") (pintype "power_in"))
      (node (ref "IC2") (pin "109") (pinfunction "__VCCD_PLL2_109") (pintype "power_in"))
      (node (ref "IC2") (pin "116") (pinfunction "__VCCINT_7_116") (pintype "power_in"))
      (node (ref "IC2") (pin "134") (pinfunction "__VCCINT_8_134") (pintype "power_in"))
      (node (ref "IC2") (pin "29") (pinfunction "__VCCINT_2_29") (pintype "power_in"))
      (node (ref "IC2") (pin "37") (pinfunction "__VCCD_PLL1_37") (pintype "power_in"))
      (node (ref "IC2") (pin "45") (pinfunction "__VCCINT_3_45") (pintype "power_in"))
      (node (ref "IC2") (pin "5") (pinfunction "__VCCINT_1_5") (pintype "power_in"))
      (node (ref "IC2") (pin "61") (pinfunction "__VCCINT_4_61") (pintype "power_in"))
      (node (ref "IC2") (pin "78") (pinfunction "__VCCINT_5_78") (pintype "power_in"))
      (node (ref "L1") (pin "P$2") (pinfunction "2_P$2") (pintype "passive"))
      (node (ref "R12") (pin "2") (pinfunction "2_2") (pintype "passive"))
      (node (ref "R19") (pin "2") (pinfunction "2_2") (pintype "passive"))
      (node (ref "TP1") (pin "TP") (pinfunction "TP_TP") (pintype "input"))
    )
    (net (code "5") (name "/+2V5") (class "Default")
      (node (ref "C27") (pin "1") (pinfunction "1_1") (pintype "passive"))
      (node (ref "C47") (pin "2") (pinfunction "2_2") (pintype "passive"))
      (node (ref "C8") (pin "1") (pinfunction "1_1") (pintype "passive"))
      (node (ref "IC2") (pin "107") (pinfunction "__VCCA2_107") (pintype "power_in"))
      (node (ref "IC2") (pin "35") (pinfunction "__VCCA1_35") (pintype "power_in"))
      (node (ref "IC8") (pin "5") (pinfunction "VOUT_5") (pintype "power_in"))
      (node (ref "TP3") (pin "TP") (pinfunction "TP_TP") (pintype "input"))
    )
    (net (code "6") (name "/+12V") (class "Default")
      (node (ref "CONN1") (pin "B22") (pinfunction "+12V_B22") (pintype "power_in"))
    )
    (net (code "7") (name "/-5V") (class "Default")
      (node (ref "CONN1") (pin "B20") (pinfunction "-5V_B20") (pintype "power_in"))
    )
    (net (code "8") (name "/-12V") (class "Default")
      (node (ref "CONN1") (pin "B23") (pinfunction "-12V_B23") (pintype "power_in"))
    )
    (net (code "9") (name "/A0") (class "Default")
      (node (ref "CONN1") (pin "A9") (pinfunction "A0_A9") (pintype "bidirectional"))
      (node (ref "RN4") (pin "1") (pinfunction "1_1") (pintype "passive"))
    )
    (net (code "10") (name "/A1") (class "Default")
      (node (ref "CONN1") (pin "A10") (pinfunction "A1_A10") (pintype "bidirectional"))
      (node (ref "RN4") (pin "2") (pinfunction "1_2") (pintype "passive"))
    )
    (net (code "11") (name "/A2") (class "Default")
      (node (ref "CONN1") (pin "A11") (pinfunction "A2_A11") (pintype "bidirectional"))
      (node (ref "RN4") (pin "3") (pinfunction "1_3") (pintype "passive"))
    )
    (net (code "12") (name "/A3") (class "Default")
      (node (ref "CONN1") (pin "A12") (pinfunction "A3_A12") (pintype "bidirectional"))
      (node (ref "RN4") (pin "4") (pinfunction "1_4") (pintype "passive"))
    )
    (net (code "13") (name "/A4") (class "Default")
      (node (ref "CONN1") (pin "A24") (pinfunction "A4_A24") (pintype "bidirectional"))
      (node (ref "RN5") (pin "4") (pinfunction "1_4") (pintype "passive"))
    )
    (net (code "14") (name "/A5") (class "Default")
      (node (ref "CONN1") (pin "A23") (pinfunction "A5_A23") (pintype "bidirectional"))
      (node (ref "RN5") (pin "3") (pinfunction "1_3") (pintype "passive"))
    )
    (net (code "15") (name "/A6") (class "Default")
      (node (ref "CONN1") (pin "A22") (pinfunction "A6_A22") (pintype "bidirectional"))
      (node (ref "RN5") (pin "2") (pinfunction "1_2") (pintype "passive"))
    )
    (net (code "16") (name "/A7") (class "Default")
      (node (ref "CONN1") (pin "A21") (pinfunction "A7_A21") (pintype "bidirectional"))
      (node (ref "RN5") (pin "1") (pinfunction "1_1") (pintype "passive"))
    )
    (net (code "17") (name "/A8") (class "Default")
      (node (ref "CONN1") (pin "B26") (pinfunction "A8_B26") (pintype "bidirectional"))
      (node (ref "RN6") (pin "1") (pinfunction "1_1") (pintype "passive"))
    )
    (net (code "18") (name "/A9") (class "Default")
      (node (ref "CONN1") (pin "A27") (pinfunction "A9_A27") (pintype "bidirectional"))
      (node (ref "RN6") (pin "2") (pinfunction "1_2") (pintype "passive"))
    )
    (net (code "19") (name "/A10") (class "Default")
      (node (ref "CONN1") (pin "B27") (pinfunction "A10_B27") (pintype "bidirectional"))
      (node (ref "RN6") (pin "3") (pinfunction "1_3") (pintype "passive"))
    )
    (net (code "20") (name "/A11") (class "Default")
      (node (ref "CONN1") (pin "A28") (pinfunction "A11_A28") (pintype "bidirectional"))
      (node (ref "RN6") (pin "4") (pinfunction "1_4") (pintype "passive"))
    )
    (net (code "21") (name "/A12") (class "Default")
      (node (ref "CONN1") (pin "A2") (pinfunction "A12_A2") (pintype "bidirectional"))
      (node (ref "RN3") (pin "4") (pinfunction "1_4") (pintype "passive"))
    )
    (net (code "22") (name "/A13") (class "Default")
      (node (ref "CONN1") (pin "B2") (pinfunction "A13_B2") (pintype "bidirectional"))
      (node (ref "RN3") (pin "3") (pinfunction "1_3") (pintype "passive"))
    )
    (net (code "23") (name "/A14") (class "Default")
      (node (ref "CONN1") (pin "A1") (pinfunction "A14_A1") (pintype "bidirectional"))
      (node (ref "RN3") (pin "2") (pinfunction "1_2") (pintype "passive"))
    )
    (net (code "24") (name "/A15") (class "Default")
      (node (ref "CONN1") (pin "B1") (pinfunction "A15_B1") (pintype "bidirectional"))
      (node (ref "RN3") (pin "1") (pinfunction "1_1") (pintype "passive"))
    )
    (net (code "25") (name "/ASDO") (class "Default")
      (node (ref "IC2") (pin "8") (pinfunction "__IO_6/FLASH_NCS/NCSO_8") (pintype "bidirectional"))
      (node (ref "U2") (pin "5") (pinfunction "ASDI_5") (pintype "input"))
    )
    (net (code "26") (name "/A_BUS_OE") (class "Default")
      (node (ref "IC10") (pin "19") (pinfunction "G_19") (pintype "input"))
      (node (ref "IC11") (pin "19") (pinfunction "G_19") (pintype "input"))
      (node (ref "IC2") (pin "10") (pinfunction "__IO_7_10") (pintype "bidirectional"))
      (node (ref "R25") (pin "2") (pinfunction "2_2") (pintype "passive"))
    )
    (net (code "27") (name "/CK") (class "Default")
      (node (ref "CONN1") (pin "A8") (pinfunction "CK_A8") (pintype "bidirectional"))
      (node (ref "RN1") (pin "1") (pinfunction "1_1") (pintype "passive"))
    )
    (net (code "28") (name "/CONF_DONE") (class "Default")
      (node (ref "IC2") (pin "92") (pinfunction "__CONF_DONE_92") (pintype "bidirectional"))
      (node (ref "TP4") (pin "TP") (pinfunction "TP_TP") (pintype "input"))
    )
    (net (code "29") (name "/CTRL_OE") (class "Default")
      (node (ref "IC2") (pin "129") (pinfunction "__IO_74_129") (pintype "bidirectional"))
      (node (ref "IC3") (pin "19") (pinfunction "G_19") (pintype "input"))
      (node (ref "R26") (pin "2") (pinfunction "2_2") (pintype "passive"))
    )
    (net (code "30") (name "/D0") (class "Default")
      (node (ref "CONN1") (pin "B6") (pinfunction "D0_B6") (pintype "bidirectional"))
      (node (ref "RN7") (pin "2") (pinfunction "1_2") (pintype "passive"))
    )
    (net (code "31") (name "/D1") (class "Default")
      (node (ref "CONN1") (pin "B7") (pinfunction "D1_B7") (pintype "bidirectional"))
      (node (ref "RN7") (pin "3") (pinfunction "1_3") (pintype "passive"))
    )
    (net (code "32") (name "/D2") (class "Default")
      (node (ref "CONN1") (pin "B8") (pinfunction "D2_B8") (pintype "bidirectional"))
      (node (ref "RN7") (pin "4") (pinfunction "1_4") (pintype "passive"))
    )
    (net (code "33") (name "/D3") (class "Default")
      (node (ref "CONN1") (pin "B11") (pinfunction "D3_B11") (pintype "bidirectional"))
      (node (ref "RN8") (pin "3") (pinfunction "1_3") (pintype "passive"))
    )
    (net (code "34") (name "/D4") (class "Default")
      (node (ref "CONN1") (pin "B12") (pinfunction "D4_B12") (pintype "bidirectional"))
      (node (ref "RN8") (pin "4") (pinfunction "1_4") (pintype "passive"))
    )
    (net (code "35") (name "/D5") (class "Default")
      (node (ref "CONN1") (pin "B10") (pinfunction "D5_B10") (pintype "bidirectional"))
      (node (ref "RN8") (pin "2") (pinfunction "1_2") (pintype "passive"))
    )
    (net (code "36") (name "/D6") (class "Default")
      (node (ref "CONN1") (pin "B9") (pinfunction "D6_B9") (pintype "bidirectional"))
      (node (ref "RN8") (pin "1") (pinfunction "1_1") (pintype "passive"))
    )
    (net (code "37") (name "/D7") (class "Default")
      (node (ref "CONN1") (pin "B3") (pinfunction "D7_B3") (pintype "bidirectional"))
      (node (ref "RN7") (pin "1") (pinfunction "1_1") (pintype "passive"))
    )
    (net (code "38") (name "/DATA0") (class "Default")
      (node (ref "IC2") (pin "13") (pinfunction "__DATA0_13") (pintype "bidirectional"))
      (node (ref "U2") (pin "2") (pinfunction "DATA_2") (pintype "output"))
    )
    (net (code "39") (name "/DCLK") (class "Default")
      (node (ref "IC2") (pin "12") (pinfunction "__DCLK_12") (pintype "input"))
      (node (ref "U2") (pin "6") (pinfunction "DCLK_6") (pintype "input"))
    )
    (net (code "40") (name "/D_BUS_DIR") (class "Default")
      (node (ref "IC2") (pin "6") (pinfunction "__IO_4/DATA/ADSO_6") (pintype "bidirectional"))
      (node (ref "IC4") (pin "1") (pinfunction "DIR_1") (pintype "input"))
    )
    (net (code "41") (name "/D_BUS_OE") (class "Default")
      (node (ref "IC2") (pin "7") (pinfunction "__IO_5_7") (pintype "bidirectional"))
      (node (ref "IC4") (pin "19") (pinfunction "G_19") (pintype "input"))
      (node (ref "R24") (pin "2") (pinfunction "2_2") (pintype "passive"))
    )
    (net (code "42") (name "/ESP_EN") (class "Default")
      (node (ref "C1") (pin "2") (pinfunction "2_2") (pintype "passive"))
      (node (ref "R2") (pin "1") (pinfunction "1_1") (pintype "passive"))
      (node (ref "S1") (pin "B2") (pinfunction "2_B2") (pintype "passive"))
      (node (ref "U1") (pin "3") (pinfunction "EN_3") (pintype "bidirectional"))
    )
    (net (code "43") (name "/ESP_IO0") (class "Default")
      (node (ref "C2") (pin "2") (pinfunction "2_2") (pintype "passive"))
      (node (ref "R3") (pin "1") (pinfunction "1_1") (pintype "passive"))
      (node (ref "S2") (pin "B2") (pinfunction "2_B2") (pintype "passive"))
      (node (ref "U1") (pin "25") (pinfunction "IO0_25") (pintype "bidirectional"))
    )
    (net (code "44") (name "/ESP_IO14") (class "Default")
      (node (ref "IC2") (pin "142") (pinfunction "__IO_82_142") (pintype "bidirectional"))
      (node (ref "U1") (pin "13") (pinfunction "IO14_13") (pintype "bidirectional"))
    )
    (net (code "45") (name "/ESP_IO25") (class "Default")
      (node (ref "IC2") (pin "137") (pinfunction "__IO_79_137") (pintype "bidirectional"))
      (node (ref "U1") (pin "10") (pinfunction "IO25_10") (pintype "bidirectional"))
    )
    (net (code "46") (name "/ESP_IO26") (class "Default")
      (node (ref "IC2") (pin "138") (pinfunction "__IO_80_138") (pintype "bidirectional"))
      (node (ref "U1") (pin "11") (pinfunction "IO26_11") (pintype "bidirectional"))
    )
    (net (code "47") (name "/ESP_IO27") (class "Default")
      (node (ref "IC2") (pin "141") (pinfunction "__IO_81_141") (pintype "bidirectional"))
      (node (ref "U1") (pin "12") (pinfunction "IO27_12") (pintype "bidirectional"))
    )
    (net (code "48") (name "/ESP_MISO") (class "Default")
      (node (ref "IC2") (pin "2") (pinfunction "__IO_2_2") (pintype "bidirectional"))
      (node (ref "U1") (pin "31") (pinfunction "IO19_31") (pintype "bidirectional"))
    )
    (net (code "49") (name "/ESP_MOSI") (class "Default")
      (node (ref "IC2") (pin "144") (pinfunction "__IO_84_144") (pintype "bidirectional"))
      (node (ref "U1") (pin "37") (pinfunction "IO23_37") (pintype "bidirectional"))
    )
    (net (code "50") (name "/ESP_NCS0") (class "Default")
      (node (ref "IC2") (pin "3") (pinfunction "__IO_3_3") (pintype "bidirectional"))
      (node (ref "U1") (pin "29") (pinfunction "IO5_29") (pintype "bidirectional"))
    )
    (net (code "51") (name "/ESP_QDH") (class "Default")
      (node (ref "IC2") (pin "1") (pinfunction "__IO_1_1") (pintype "bidirectional"))
      (node (ref "U1") (pin "33") (pinfunction "IO21_33") (pintype "bidirectional"))
    )
    (net (code "52") (name "/ESP_QWP") (class "Default")
      (node (ref "IC2") (pin "143") (pinfunction "__IO_83_143") (pintype "bidirectional"))
      (node (ref "U1") (pin "36") (pinfunction "IO22_36") (pintype "bidirectional"))
    )
    (net (code "53") (name "/ESP_RX") (class "Default")
      (node (ref "IC7") (pin "6") (pinfunction "TX_6") (pintype "output"))
      (node (ref "U1") (pin "34") (pinfunction "RXD0_34") (pintype "bidirectional"))
    )
    (net (code "54") (name "/ESP_SCK") (class "Default")
      (node (ref "IC2") (pin "23") (pinfunction "__CLK1_23") (pintype "input"))
      (node (ref "U1") (pin "30") (pinfunction "IO18_30") (pintype "bidirectional"))
    )
    (net (code "55") (name "/ESP_TX") (class "Default")
      (node (ref "IC7") (pin "7") (pinfunction "RX_7") (pintype "input"))
      (node (ref "U1") (pin "35") (pinfunction "TXD0_35") (pintype "bidirectional"))
    )
    (net (code "56") (name "/FORCE_INT") (class "Default")
      (node (ref "IC2") (pin "53") (pinfunction "__IO_26_53") (pintype "bidirectional"))
      (node (ref "Q2") (pin "1") (pinfunction "G_1") (pintype "passive"))
    )
    (net (code "57") (name "/FORCE_RESET") (class "Default")
      (node (ref "IC2") (pin "67") (pinfunction "__IO_35_67") (pintype "bidirectional"))
      (node (ref "Q1") (pin "1") (pinfunction "G_1") (pintype "passive"))
    )
    (net (code "58") (name "/FORCE_ROMCS") (class "Default")
      (node (ref "IC2") (pin "132") (pinfunction "__IO_75_132") (pintype "bidirectional"))
      (node (ref "Q3") (pin "1") (pinfunction "G_1") (pintype "passive"))
    )
    (net (code "59") (name "/FR1") (class "Default")
      (node (ref "Q3") (pin "3") (pinfunction "D_3") (pintype "passive"))
      (node (ref "Q4") (pin "1") (pinfunction "G_1") (pintype "passive"))
      (node (ref "R5") (pin "2") (pinfunction "2_2") (pintype "passive"))
    )
    (net (code "60") (name "/INT") (class "Default")
      (node (ref "CONN1") (pin "B13") (pinfunction "INT_B13") (pintype "bidirectional"))
      (node (ref "Q2") (pin "3") (pinfunction "D_3") (pintype "passive"))
      (node (ref "RN1") (pin "2") (pinfunction "1_2") (pintype "passive"))
    )
    (net (code "61") (name "/IORQ") (class "Default")
      (node (ref "CONN1") (pin "B17") (pinfunction "IORQ_B17") (pintype "bidirectional"))
      (node (ref "RN1") (pin "4") (pinfunction "1_4") (pintype "passive"))
    )
    (net (code "62") (name "/LED1") (class "Default")
      (node (ref "R21") (pin "2") (pinfunction "2_2") (pintype "passive"))
      (node (ref "U1") (pin "8") (pinfunction "IO32_8") (pintype "bidirectional"))
    )
    (net (code "63") (name "/LED2") (class "Default")
      (node (ref "R22") (pin "2") (pinfunction "2_2") (pintype "passive"))
      (node (ref "U1") (pin "9") (pinfunction "IO33_9") (pintype "bidirectional"))
    )
    (net (code "64") (name "/M1") (class "Default")
      (node (ref "CONN1") (pin "B24") (pinfunction "M1_B24") (pintype "bidirectional"))
      (node (ref "RN2") (pin "3") (pinfunction "1_3") (pintype "passive"))
    )
    (net (code "65") (name "/MREQ") (class "Default")
      (node (ref "CONN1") (pin "B16") (pinfunction "MREQ_B16") (pintype "bidirectional"))
      (node (ref "RN1") (pin "3") (pinfunction "1_3") (pintype "passive"))
    )
    (net (code "66") (name "/NCONFIG") (class "Default")
      (node (ref "IC2") (pin "14") (pinfunction "__NCONFIG_14") (pintype "bidirectional"))
      (node (ref "R7") (pin "1") (pinfunction "1_1") (pintype "passive"))
    )
    (net (code "67") (name "/NCSO") (class "Default")
      (node (ref "IC2") (pin "11") (pinfunction "__IO_8_11") (pintype "bidirectional"))
      (node (ref "U2") (pin "1") (pinfunction "NCS_1") (pintype "input"))
    )
    (net (code "68") (name "/RD") (class "Default")
      (node (ref "CONN1") (pin "B18") (pinfunction "RD_B18") (pintype "bidirectional"))
      (node (ref "RN2") (pin "1") (pinfunction "1_1") (pintype "passive"))
    )
    (net (code "69") (name "/RESET") (class "Default")
      (node (ref "CONN1") (pin "A20") (pinfunction "RESET_A20") (pintype "bidirectional"))
      (node (ref "Q1") (pin "3") (pinfunction "D_3") (pintype "passive"))
    )
    (net (code "70") (name "/RFSH") (class "Default")
      (node (ref "CONN1") (pin "B25") (pinfunction "RFSH_B25") (pintype "bidirectional"))
      (node (ref "RN2") (pin "4") (pinfunction "1_4") (pintype "passive"))
    )
    (net (code "71") (name "/ROMCS") (class "Default")
      (node (ref "CONN1") (pin "A25") (pinfunction "ROMCS_A25") (pintype "bidirectional"))
      (node (ref "Q4") (pin "3") (pinfunction "D_3") (pintype "passive"))
    )
    (net (code "72") (name "/SDMMC_CK") (class "Default")
      (node (ref "SD1") (pin "5") (pinfunction "CLK(SCLK)_5") (pintype "input"))
      (node (ref "U1") (pin "20") (pinfunction "CLK_20") (pintype "bidirectional"))
    )
    (net (code "73") (name "/SDMMC_CMD") (class "Default")
      (node (ref "SD1") (pin "3") (pinfunction "CMD(DI)_3") (pintype "bidirectional"))
      (node (ref "U1") (pin "19") (pinfunction "CMD_19") (pintype "bidirectional"))
    )
    (net (code "74") (name "/SDMMC_D0") (class "Default")
      (node (ref "SD1") (pin "7") (pinfunction "DAT0(DO)_7") (pintype "bidirectional"))
      (node (ref "U1") (pin "21") (pinfunction "SDO_21") (pintype "bidirectional"))
    )
    (net (code "75") (name "/SDMMC_D1") (class "Default")
      (node (ref "SD1") (pin "8") (pinfunction "DAT1_8") (pintype "bidirectional"))
      (node (ref "U1") (pin "22") (pinfunction "SD1_22") (pintype "bidirectional"))
    )
    (net (code "76") (name "/SDMMC_D2") (class "Default")
      (node (ref "SD1") (pin "1") (pinfunction "DAT2_1") (pintype "bidirectional"))
      (node (ref "U1") (pin "17") (pinfunction "SD2_17") (pintype "bidirectional"))
    )
    (net (code "77") (name "/SDMMC_D3") (class "Default")
      (node (ref "SD1") (pin "2") (pinfunction "CD/DAT3(~{CS})_2") (pintype "bidirectional"))
      (node (ref "U1") (pin "18") (pinfunction "SD3_18") (pintype "bidirectional"))
    )
    (net (code "78") (name "/SDMMC_DET") (class "Default")
      (node (ref "R1") (pin "2") (pinfunction "2_2") (pintype "passive"))
      (node (ref "SD1") (pin "A") (pinfunction "A_A") (pintype "passive"))
      (node (ref "U1") (pin "23") (pinfunction "IO15_23") (pintype "bidirectional"))
    )
    (net (code "79") (name "/SD_A0") (class "Default")
      (node (ref "IC2") (pin "87") (pinfunction "__IO_51_87") (pintype "bidirectional"))
      (node (ref "IC9") (pin "23") (pinfunction "A0_23") (pintype "input"))
    )
    (net (code "80") (name "/SD_A1") (class "Default")
      (node (ref "IC2") (pin "86") (pinfunction "__IO_50_86") (pintype "bidirectional"))
      (node (ref "IC9") (pin "24") (pinfunction "A1_24") (pintype "input"))
    )
    (net (code "81") (name "/SD_A2") (class "Default")
      (node (ref "IC2") (pin "85") (pinfunction "__IO_49_85") (pintype "bidirectional"))
      (node (ref "IC9") (pin "25") (pinfunction "A2_25") (pintype "input"))
    )
    (net (code "82") (name "/SD_A3") (class "Default")
      (node (ref "IC2") (pin "84") (pinfunction "__IO_48_84") (pintype "bidirectional"))
      (node (ref "IC9") (pin "26") (pinfunction "A3_26") (pintype "input"))
    )
    (net (code "83") (name "/SD_A4") (class "Default")
      (node (ref "IC2") (pin "76") (pinfunction "__IO_44_76") (pintype "bidirectional"))
      (node (ref "IC9") (pin "29") (pinfunction "A4_29") (pintype "input"))
    )
    (net (code "84") (name "/SD_A5") (class "Default")
      (node (ref "IC2") (pin "77") (pinfunction "__IO_45_77") (pintype "bidirectional"))
      (node (ref "IC9") (pin "30") (pinfunction "A5_30") (pintype "input"))
    )
    (net (code "85") (name "/SD_A6") (class "Default")
      (node (ref "IC2") (pin "80") (pinfunction "__IO_46_80") (pintype "bidirectional"))
      (node (ref "IC9") (pin "31") (pinfunction "A6_31") (pintype "input"))
    )
    (net (code "86") (name "/SD_A7") (class "Default")
      (node (ref "IC2") (pin "83") (pinfunction "__IO_47_83") (pintype "bidirectional"))
      (node (ref "IC9") (pin "32") (pinfunction "A7_32") (pintype "input"))
    )
    (net (code "87") (name "/SD_A8") (class "Default")
      (node (ref "IC2") (pin "120") (pinfunction "__IO_67_120") (pintype "bidirectional"))
      (node (ref "IC9") (pin "33") (pinfunction "A8_33") (pintype "input"))
    )
    (net (code "88") (name "/SD_A9") (class "Default")
      (node (ref "IC2") (pin "121") (pinfunction "__IO_68_121") (pintype "bidirectional"))
      (node (ref "IC9") (pin "34") (pinfunction "A9_34") (pintype "input"))
    )
    (net (code "89") (name "/SD_A10") (class "Default")
      (node (ref "IC2") (pin "98") (pinfunction "__IO_52_98") (pintype "bidirectional"))
      (node (ref "IC9") (pin "22") (pinfunction "A10_22") (pintype "input"))
    )
    (net (code "90") (name "/SD_A11") (class "Default")
      (node (ref "IC2") (pin "124") (pinfunction "__IO_69_124") (pintype "bidirectional"))
      (node (ref "IC9") (pin "35") (pinfunction "A11_35") (pintype "input"))
    )
    (net (code "91") (name "/SD_A12") (class "Default")
      (node (ref "IC2") (pin "125") (pinfunction "__IO_70_125") (pintype "bidirectional"))
      (node (ref "IC9") (pin "36") (pinfunction "A12_36") (pintype "input"))
    )
    (net (code "92") (name "/SD_BA0") (class "Default")
      (node (ref "IC2") (pin "100") (pinfunction "__IO_54_100") (pintype "bidirectional"))
      (node (ref "IC9") (pin "20") (pinfunction "BA0_20") (pintype "input"))
    )
    (net (code "93") (name "/SD_BA1") (class "Default")
      (node (ref "IC2") (pin "99") (pinfunction "__IO_53_99") (pintype "bidirectional"))
      (node (ref "IC9") (pin "21") (pinfunction "BA1_21") (pintype "input"))
    )
    (net (code "94") (name "/SD_CK") (class "Default")
      (node (ref "IC2") (pin "127") (pinfunction "__IO_72_127") (pintype "bidirectional"))
      (node (ref "IC9") (pin "38") (pinfunction "CLK_38") (pintype "input"))
    )
    (net (code "95") (name "/SD_CKE") (class "Default")
      (node (ref "IC2") (pin "126") (pinfunction "__IO_71_126") (pintype "bidirectional"))
      (node (ref "IC9") (pin "37") (pinfunction "CKE_37") (pintype "input"))
    )
    (net (code "96") (name "/SD_CS") (class "Default")
      (node (ref "IC2") (pin "101") (pinfunction "__IO_55_101") (pintype "bidirectional"))
      (node (ref "IC9") (pin "19") (pinfunction "\\CS_19") (pintype "input"))
    )
    (net (code "97") (name "/SD_DQ0") (class "Default")
      (node (ref "IC2") (pin "119") (pinfunction "__IO_66_119") (pintype "bidirectional"))
      (node (ref "IC9") (pin "2") (pinfunction "DQ0_2") (pintype "tri_state"))
    )
    (net (code "98") (name "/SD_DQ1") (class "Default")
      (node (ref "IC2") (pin "115") (pinfunction "__IO_65_115") (pintype "bidirectional"))
      (node (ref "IC9") (pin "4") (pinfunction "DQ1_4") (pintype "tri_state"))
    )
    (net (code "99") (name "/SD_DQ2") (class "Default")
      (node (ref "IC2") (pin "114") (pinfunction "__IO_64_114") (pintype "bidirectional"))
      (node (ref "IC9") (pin "5") (pinfunction "DQ2_5") (pintype "tri_state"))
    )
    (net (code "100") (name "/SD_DQ3") (class "Default")
      (node (ref "IC2") (pin "113") (pinfunction "__IO_63_113") (pintype "bidirectional"))
      (node (ref "IC9") (pin "7") (pinfunction "DQ3_7") (pintype "tri_state"))
    )
    (net (code "101") (name "/SD_DQ4") (class "Default")
      (node (ref "IC2") (pin "112") (pinfunction "__IO_62_112") (pintype "bidirectional"))
      (node (ref "IC9") (pin "8") (pinfunction "DQ4_8") (pintype "tri_state"))
    )
    (net (code "102") (name "/SD_DQ5") (class "Default")
      (node (ref "IC2") (pin "111") (pinfunction "__IO_61_111") (pintype "bidirectional"))
      (node (ref "IC9") (pin "10") (pinfunction "DQ5_10") (pintype "tri_state"))
    )
    (net (code "103") (name "/SD_DQ6") (class "Default")
      (node (ref "IC2") (pin "110") (pinfunction "__IO_60_110") (pintype "bidirectional"))
      (node (ref "IC9") (pin "11") (pinfunction "DQ6_11") (pintype "tri_state"))
    )
    (net (code "104") (name "/SD_DQ7") (class "Default")
      (node (ref "IC2") (pin "106") (pinfunction "__IO_59_106") (pintype "bidirectional"))
      (node (ref "IC9") (pin "13") (pinfunction "DQ7_13") (pintype "tri_state"))
    )
    (net (code "105") (name "/SD_DQMH") (class "Default")
      (node (ref "IC2") (pin "128") (pinfunction "__IO_73_128") (pintype "bidirectional"))
      (node (ref "IC9") (pin "39") (pinfunction "DQMH_39") (pintype "input"))
    )
    (net (code "106") (name "/SD_NCAS") (class "Default")
      (node (ref "IC2") (pin "104") (pinfunction "__IO_57_104") (pintype "bidirectional"))
      (node (ref "IC9") (pin "17") (pinfunction "~{CAS}_17") (pintype "input"))
    )
    (net (code "107") (name "/SD_NRAS") (class "Default")
      (node (ref "IC2") (pin "103") (pinfunction "__IO_56_103") (pintype "bidirectional"))
      (node (ref "IC9") (pin "18") (pinfunction "~{RAS}_18") (pintype "input"))
    )
    (net (code "108") (name "/SD_NWE") (class "Default")
      (node (ref "IC2") (pin "105") (pinfunction "__IO_58_105") (pintype "bidirectional"))
      (node (ref "IC9") (pin "16") (pinfunction "~{WE}_16") (pintype "input"))
    )
    (net (code "109") (name "/SW1") (class "Default")
      (node (ref "C42") (pin "1") (pinfunction "1_1") (pintype "passive"))
      (node (ref "IC5") (pin "3") (pinfunction "SW_3") (pintype "passive"))
      (node (ref "L1") (pin "P$1") (pinfunction "1_P$1") (pintype "passive"))
    )
    (net (code "110") (name "/SW2") (class "Default")
      (node (ref "C43") (pin "1") (pinfunction "1_1") (pintype "passive"))
      (node (ref "IC6") (pin "3") (pinfunction "SW_3") (pintype "passive"))
      (node (ref "L2") (pin "P$1") (pinfunction "1_P$1") (pintype "passive"))
    )
    (net (code "111") (name "/SWITCH") (class "Default")
      (node (ref "R4") (pin "1") (pinfunction "1_1") (pintype "passive"))
      (node (ref "S3") (pin "B2") (pinfunction "2_B2") (pintype "passive"))
      (node (ref "U1") (pin "6") (pinfunction "IO34_6") (pintype "input"))
    )
    (net (code "112") (name "/TCK") (class "Default")
      (node (ref "CONN2") (pin "1") (pinfunction "1_1") (pintype "passive"))
      (node (ref "IC2") (pin "16") (pinfunction "__TCK_16") (pintype "bidirectional"))
      (node (ref "R10") (pin "1") (pinfunction "1_1") (pintype "passive"))
    )
    (net (code "113") (name "/TDI") (class "Default")
      (node (ref "CONN2") (pin "9") (pinfunction "9_9") (pintype "passive"))
      (node (ref "IC2") (pin "15") (pinfunction "__TDI_15") (pintype "bidirectional"))
    )
    (net (code "114") (name "/TDO") (class "Default")
      (node (ref "CONN2") (pin "3") (pinfunction "3_3") (pintype "passive"))
      (node (ref "IC2") (pin "20") (pinfunction "__TDO_20") (pintype "bidirectional"))
      (node (ref "R8") (pin "1") (pinfunction "1_1") (pintype "passive"))
    )
    (net (code "115") (name "/TMS") (class "Default")
      (node (ref "CONN2") (pin "5") (pinfunction "5_5") (pintype "passive"))
      (node (ref "IC2") (pin "18") (pinfunction "__TMS_18") (pintype "bidirectional"))
      (node (ref "R9") (pin "1") (pinfunction "1_1") (pintype "passive"))
    )
    (net (code "116") (name "/VREG") (class "Default")
      (node (ref "C31") (pin "2") (pinfunction "2_2") (pintype "passive"))
      (node (ref "C32") (pin "2") (pinfunction "2_2") (pintype "passive"))
      (node (ref "C33") (pin "2") (pinfunction "2_2") (pintype "passive"))
      (node (ref "C34") (pin "2") (pinfunction "2_2") (pintype "passive"))
      (node (ref "IC5") (pin "2") (pinfunction "IN_2") (pintype "power_in"))
      (node (ref "IC6") (pin "2") (pinfunction "IN_2") (pintype "power_in"))
      (node (ref "SJ1") (pin "2") (pinfunction "2_2") (pintype "passive"))
    )
    (net (code "117") (name "/WR") (class "Default")
      (node (ref "CONN1") (pin "B19") (pinfunction "WR_B19") (pintype "bidirectional"))
      (node (ref "RN2") (pin "2") (pinfunction "1_2") (pintype "passive"))
    )
    (net (code "118") (name "/XA0") (class "Default")
      (node (ref "IC11") (pin "11") (pinfunction "B8_11") (pintype "bidirectional"))
      (node (ref "IC2") (pin "75") (pinfunction "__IO_43_75") (pintype "bidirectional"))
    )
    (net (code "119") (name "/XA1") (class "Default")
      (node (ref "IC11") (pin "12") (pinfunction "B7_12") (pintype "bidirectional"))
      (node (ref "IC2") (pin "74") (pinfunction "__IO_42_74") (pintype "bidirectional"))
    )
    (net (code "120") (name "/XA2") (class "Default")
      (node (ref "IC11") (pin "13") (pinfunction "B6_13") (pintype "bidirectional"))
      (node (ref "IC2") (pin "73") (pinfunction "__IO_41_73") (pintype "bidirectional"))
    )
    (net (code "121") (name "/XA3") (class "Default")
      (node (ref "IC11") (pin "14") (pinfunction "B5_14") (pintype "bidirectional"))
      (node (ref "IC2") (pin "72") (pinfunction "__IO_40_72") (pintype "bidirectional"))
    )
    (net (code "122") (name "/XA4") (class "Default")
      (node (ref "IC11") (pin "15") (pinfunction "B4_15") (pintype "bidirectional"))
      (node (ref "IC2") (pin "71") (pinfunction "__IO_39_71") (pintype "bidirectional"))
    )
    (net (code "123") (name "/XA5") (class "Default")
      (node (ref "IC11") (pin "16") (pinfunction "B3_16") (pintype "bidirectional"))
      (node (ref "IC2") (pin "70") (pinfunction "__IO_38_70") (pintype "bidirectional"))
    )
    (net (code "124") (name "/XA6") (class "Default")
      (node (ref "IC11") (pin "17") (pinfunction "B2_17") (pintype "bidirectional"))
      (node (ref "IC2") (pin "69") (pinfunction "__IO_37_69") (pintype "bidirectional"))
    )
    (net (code "125") (name "/XA7") (class "Default")
      (node (ref "IC11") (pin "18") (pinfunction "B1_18") (pintype "bidirectional"))
      (node (ref "IC2") (pin "68") (pinfunction "__IO_36_68") (pintype "bidirectional"))
    )
    (net (code "126") (name "/XA8") (class "Default")
      (node (ref "IC10") (pin "11") (pinfunction "B8_11") (pintype "bidirectional"))
      (node (ref "IC2") (pin "39") (pinfunction "__IO_17_39") (pintype "bidirectional"))
    )
    (net (code "127") (name "/XA9") (class "Default")
      (node (ref "IC10") (pin "12") (pinfunction "B7_12") (pintype "bidirectional"))
      (node (ref "IC2") (pin "38") (pinfunction "__IO_16_38") (pintype "bidirectional"))
    )
    (net (code "128") (name "/XA10") (class "Default")
      (node (ref "IC10") (pin "13") (pinfunction "B6_13") (pintype "bidirectional"))
      (node (ref "IC2") (pin "34") (pinfunction "__IO_15_34") (pintype "bidirectional"))
    )
    (net (code "129") (name "/XA11") (class "Default")
      (node (ref "IC10") (pin "14") (pinfunction "B5_14") (pintype "bidirectional"))
      (node (ref "IC2") (pin "33") (pinfunction "__IO_14_33") (pintype "bidirectional"))
    )
    (net (code "130") (name "/XA12") (class "Default")
      (node (ref "IC10") (pin "15") (pinfunction "B4_15") (pintype "bidirectional"))
      (node (ref "IC2") (pin "32") (pinfunction "__IO_13_32") (pintype "bidirectional"))
    )
    (net (code "131") (name "/XA13") (class "Default")
      (node (ref "IC10") (pin "16") (pinfunction "B3_16") (pintype "bidirectional"))
      (node (ref "IC2") (pin "31") (pinfunction "__IO_12_31") (pintype "bidirectional"))
    )
    (net (code "132") (name "/XA14") (class "Default")
      (node (ref "IC10") (pin "17") (pinfunction "B2_17") (pintype "bidirectional"))
      (node (ref "IC2") (pin "30") (pinfunction "__IO_11_30") (pintype "bidirectional"))
    )
    (net (code "133") (name "/XA15") (class "Default")
      (node (ref "IC10") (pin "18") (pinfunction "B1_18") (pintype "bidirectional"))
      (node (ref "IC2") (pin "28") (pinfunction "__IO_10_28") (pintype "bidirectional"))
    )
    (net (code "134") (name "/XCK") (class "Default")
      (node (ref "IC2") (pin "54") (pinfunction "__IO_27_54") (pintype "bidirectional"))
      (node (ref "IC3") (pin "18") (pinfunction "B1_18") (pintype "bidirectional"))
    )
    (net (code "135") (name "/XD0") (class "Default")
      (node (ref "IC2") (pin "43") (pinfunction "__IO_19_43") (pintype "bidirectional"))
      (node (ref "IC4") (pin "17") (pinfunction "B2_17") (pintype "bidirectional"))
    )
    (net (code "136") (name "/XD1") (class "Default")
      (node (ref "IC2") (pin "44") (pinfunction "__IO_20_44") (pintype "bidirectional"))
      (node (ref "IC4") (pin "16") (pinfunction "B3_16") (pintype "bidirectional"))
    )
    (net (code "137") (name "/XD2") (class "Default")
      (node (ref "IC2") (pin "46") (pinfunction "__IO_21_46") (pintype "bidirectional"))
      (node (ref "IC4") (pin "15") (pinfunction "B4_15") (pintype "bidirectional"))
    )
    (net (code "138") (name "/XD3") (class "Default")
      (node (ref "IC2") (pin "51") (pinfunction "__IO_24_51") (pintype "bidirectional"))
      (node (ref "IC4") (pin "12") (pinfunction "B7_12") (pintype "bidirectional"))
    )
    (net (code "139") (name "/XD4") (class "Default")
      (node (ref "IC2") (pin "52") (pinfunction "__IO_25_52") (pintype "bidirectional"))
      (node (ref "IC4") (pin "11") (pinfunction "B8_11") (pintype "bidirectional"))
    )
    (net (code "140") (name "/XD5") (class "Default")
      (node (ref "IC2") (pin "50") (pinfunction "__IO_23_50") (pintype "bidirectional"))
      (node (ref "IC4") (pin "13") (pinfunction "B6_13") (pintype "bidirectional"))
    )
    (net (code "141") (name "/XD6") (class "Default")
      (node (ref "IC2") (pin "49") (pinfunction "__IO_22_49") (pintype "bidirectional"))
      (node (ref "IC4") (pin "14") (pinfunction "B5_14") (pintype "bidirectional"))
    )
    (net (code "142") (name "/XD7") (class "Default")
      (node (ref "IC2") (pin "42") (pinfunction "__IO_18_42") (pintype "bidirectional"))
      (node (ref "IC4") (pin "18") (pinfunction "B1_18") (pintype "bidirectional"))
    )
    (net (code "143") (name "/XINT") (class "Default")
      (node (ref "IC2") (pin "55") (pinfunction "__IO_28_55") (pintype "bidirectional"))
      (node (ref "IC3") (pin "17") (pinfunction "B2_17") (pintype "bidirectional"))
    )
    (net (code "144") (name "/XIORQ") (class "Default")
      (node (ref "IC2") (pin "59") (pinfunction "__IO_30_59") (pintype "bidirectional"))
      (node (ref "IC3") (pin "15") (pinfunction "B4_15") (pintype "bidirectional"))
    )
    (net (code "145") (name "/XM1") (class "Default")
      (node (ref "IC2") (pin "65") (pinfunction "__IO_33_65") (pintype "bidirectional"))
      (node (ref "IC3") (pin "12") (pinfunction "B7_12") (pintype "bidirectional"))
    )
    (net (code "146") (name "/XMREQ") (class "Default")
      (node (ref "IC2") (pin "58") (pinfunction "__IO_29_58") (pintype "bidirectional"))
      (node (ref "IC3") (pin "16") (pinfunction "B3_16") (pintype "bidirectional"))
    )
    (net (code "147") (name "/XRD") (class "Default")
      (node (ref "IC2") (pin "60") (pinfunction "__IO_31_60") (pintype "bidirectional"))
      (node (ref "IC3") (pin "14") (pinfunction "B5_14") (pintype "bidirectional"))
    )
    (net (code "148") (name "/XRFSH") (class "Default")
      (node (ref "IC2") (pin "66") (pinfunction "__IO_34_66") (pintype "bidirectional"))
      (node (ref "IC3") (pin "11") (pinfunction "B8_11") (pintype "bidirectional"))
    )
    (net (code "149") (name "/XWR") (class "Default")
      (node (ref "IC2") (pin "64") (pinfunction "__IO_32_64") (pintype "bidirectional"))
      (node (ref "IC3") (pin "13") (pinfunction "B6_13") (pintype "bidirectional"))
    )
    (net (code "150") (name "GND") (class "Default")
      (node (ref "C1") (pin "1") (pinfunction "1_1") (pintype "passive"))
      (node (ref "C10") (pin "2") (pinfunction "2_2") (pintype "passive"))
      (node (ref "C11") (pin "2") (pinfunction "2_2") (pintype "passive"))
      (node (ref "C12") (pin "2") (pinfunction "2_2") (pintype "passive"))
      (node (ref "C13") (pin "2") (pinfunction "2_2") (pintype "passive"))
      (node (ref "C14") (pin "2") (pinfunction "2_2") (pintype "passive"))
      (node (ref "C15") (pin "2") (pinfunction "2_2") (pintype "passive"))
      (node (ref "C16") (pin "2") (pinfunction "2_2") (pintype "passive"))
      (node (ref "C17") (pin "2") (pinfunction "2_2") (pintype "passive"))
      (node (ref "C18") (pin "2") (pinfunction "2_2") (pintype "passive"))
      (node (ref "C19") (pin "2") (pinfunction "2_2") (pintype "passive"))
      (node (ref "C2") (pin "1") (pinfunction "1_1") (pintype "passive"))
      (node (ref "C20") (pin "2") (pinfunction "2_2") (pintype "passive"))
      (node (ref "C21") (pin "2") (pinfunction "2_2") (pintype "passive"))
      (node (ref "C22") (pin "2") (pinfunction "2_2") (pintype "passive"))
      (node (ref "C23") (pin "2") (pinfunction "2_2") (pintype "passive"))
      (node (ref "C24") (pin "2") (pinfunction "2_2") (pintype "passive"))
      (node (ref "C25") (pin "2") (pinfunction "2_2") (pintype "passive"))
      (node (ref "C26") (pin "2") (pinfunction "2_2") (pintype "passive"))
      (node (ref "C27") (pin "2") (pinfunction "2_2") (pintype "passive"))
      (node (ref "C28") (pin "2") (pinfunction "2_2") (pintype "passive"))
      (node (ref "C29") (pin "2") (pinfunction "2_2") (pintype "passive"))
      (node (ref "C3") (pin "2") (pinfunction "2_2") (pintype "passive"))
      (node (ref "C30") (pin "2") (pinfunction "2_2") (pintype "passive"))
      (node (ref "C31") (pin "1") (pinfunction "1_1") (pintype "passive"))
      (node (ref "C32") (pin "1") (pinfunction "1_1") (pintype "passive"))
      (node (ref "C33") (pin "1") (pinfunction "1_1") (pintype "passive"))
      (node (ref "C34") (pin "1") (pinfunction "1_1") (pintype "passive"))
      (node (ref "C35") (pin "1") (pinfunction "1_1") (pintype "passive"))
      (node (ref "C36") (pin "1") (pinfunction "1_1") (pintype "passive"))
      (node (ref "C37") (pin "2") (pinfunction "2_2") (pintype "passive"))
      (node (ref "C38") (pin "1") (pinfunction "1_1") (pintype "passive"))
      (node (ref "C39") (pin "1") (pinfunction "1_1") (pintype "passive"))
      (node (ref "C4") (pin "2") (pinfunction "2_2") (pintype "passive"))
      (node (ref "C40") (pin "2") (pinfunction "2_2") (pintype "passive"))
      (node (ref "C41") (pin "2") (pinfunction "2_2") (pintype "passive"))
      (node (ref "C45") (pin "1") (pinfunction "1_1") (pintype "passive"))
      (node (ref "C46") (pin "1") (pinfunction "1_1") (pintype "passive"))
      (node (ref "C47") (pin "1") (pinfunction "1_1") (pintype "passive"))
      (node (ref "C48") (pin "2") (pinfunction "2_2") (pintype "passive"))
      (node (ref "C49") (pin "2") (pinfunction "2_2") (pintype "passive"))
      (node (ref "C5") (pin "2") (pinfunction "2_2") (pintype "passive"))
      (node (ref "C50") (pin "2") (pinfunction "2_2") (pintype "passive"))
      (node (ref "C51") (pin "2") (pinfunction "2_2") (pintype "passive"))
      (node (ref "C52") (pin "2") (pinfunction "2_2") (pintype "passive"))
      (node (ref "C53") (pin "2") (pinfunction "2_2") (pintype "passive"))
      (node (ref "C54") (pin "2") (pinfunction "2_2") (pintype "passive"))
      (node (ref "C55") (pin "2") (pinfunction "2_2") (pintype "passive"))
      (node (ref "C56") (pin "2") (pinfunction "2_2") (pintype "passive"))
      (node (ref "C57") (pin "MINUS") (pinfunction "-_MINUS") (pintype "passive"))
      (node (ref "C6") (pin "2") (pinfunction "2_2") (pintype "passive"))
      (node (ref "C60") (pin "MINUS") (pinfunction "-_MINUS") (pintype "passive"))
      (node (ref "C7") (pin "2") (pinfunction "2_2") (pintype "passive"))
      (node (ref "C8") (pin "2") (pinfunction "2_2") (pintype "passive"))
      (node (ref "C9") (pin "2") (pinfunction "2_2") (pintype "passive"))
      (node (ref "CONN1") (pin "A14") (pinfunction "GND_A14") (pintype "power_in"))
      (node (ref "CONN1") (pin "A6") (pinfunction "GND_A6") (pintype "power_in"))
      (node (ref "CONN1") (pin "A7") (pinfunction "GND_A7") (pintype "power_in"))
      (node (ref "CONN2") (pin "10") (pinfunction "10_10") (pintype "passive"))
      (node (ref "CONN2") (pin "2") (pinfunction "2_2") (pintype "passive"))
      (node (ref "IC10") (pin "10") (pinfunction "GND_10") (pintype "power_in"))
      (node (ref "IC11") (pin "10") (pinfunction "GND_10") (pintype "power_in"))
      (node (ref "IC2") (pin "108") (pinfunction "__GNDA2_108") (pintype "power_in"))
      (node (ref "IC2") (pin "118") (pinfunction "__GND_12_118") (pintype "power_in"))
      (node (ref "IC2") (pin "123") (pinfunction "__GND_13_123") (pintype "power_in"))
      (node (ref "IC2") (pin "131") (pinfunction "__GND_14_131") (pintype "power_in"))
      (node (ref "IC2") (pin "140") (pinfunction "__GND_15_140") (pintype "power_in"))
      (node (ref "IC2") (pin "145") (pinfunction "TP_145") (pintype "bidirectional"))
      (node (ref "IC2") (pin "19") (pinfunction "__GND_2_19") (pintype "power_in"))
      (node (ref "IC2") (pin "21") (pinfunction "__NCE_21") (pintype "bidirectional"))
      (node (ref "IC2") (pin "22") (pinfunction "__GND_3_22") (pintype "power_in"))
      (node (ref "IC2") (pin "27") (pinfunction "__GND_4_27") (pintype "power_in"))
      (node (ref "IC2") (pin "36") (pinfunction "__GNDA1_36") (pintype "power_in"))
      (node (ref "IC2") (pin "4") (pinfunction "__GND_1_4") (pintype "power_in"))
      (node (ref "IC2") (pin "41") (pinfunction "__GND_5_41") (pintype "power_in"))
      (node (ref "IC2") (pin "48") (pinfunction "__GND_6_48") (pintype "power_in"))
      (node (ref "IC2") (pin "57") (pinfunction "__GND_7_57") (pintype "power_in"))
      (node (ref "IC2") (pin "63") (pinfunction "__GND_8_63") (pintype "power_in"))
      (node (ref "IC2") (pin "79") (pinfunction "__GND_9_79") (pintype "power_in"))
      (node (ref "IC2") (pin "82") (pinfunction "__GND_10_82") (pintype "power_in"))
      (node (ref "IC2") (pin "95") (pinfunction "__GND_11_95") (pintype "power_in"))
      (node (ref "IC2") (pin "96") (pinfunction "__MSEL1_96") (pintype "bidirectional"))
      (node (ref "IC3") (pin "10") (pinfunction "GND_10") (pintype "power_in"))
      (node (ref "IC4") (pin "10") (pinfunction "GND_10") (pintype "power_in"))
      (node (ref "IC5") (pin "4") (pinfunction "GND_4") (pintype "power_in"))
      (node (ref "IC6") (pin "4") (pinfunction "GND_4") (pintype "power_in"))
      (node (ref "IC7") (pin "3") (pinfunction "GND_3") (pintype "power_in"))
      (node (ref "IC8") (pin "2") (pinfunction "GND_2") (pintype "power_in"))
      (node (ref "IC9") (pin "12") (pinfunction "VSSQ_12") (pintype "power_in"))
      (node (ref "IC9") (pin "28") (pinfunction "VSS_28") (pintype "power_in"))
      (node (ref "IC9") (pin "41") (pinfunction "VSS_41") (pintype "power_in"))
      (node (ref "IC9") (pin "46") (pinfunction "VSSQ_46") (pintype "power_in"))
      (node (ref "IC9") (pin "52") (pinfunction "VSSQ_52") (pintype "power_in"))
      (node (ref "IC9") (pin "54") (pinfunction "VSS_54") (pintype "power_in"))
      (node (ref "IC9") (pin "6") (pinfunction "VSSQ_6") (pintype "power_in"))
      (node (ref "Q1") (pin "2") (pinfunction "S_2") (pintype "passive"))
      (node (ref "Q2") (pin "2") (pinfunction "S_2") (pintype "passive"))
      (node (ref "Q3") (pin "2") (pinfunction "S_2") (pintype "passive"))
      (node (ref "R10") (pin "2") (pinfunction "2_2") (pintype "passive"))
      (node (ref "R17") (pin "1") (pinfunction "1_1") (pintype "passive"))
      (node (ref "R18") (pin "1") (pinfunction "1_1") (pintype "passive"))
      (node (ref "R23") (pin "2") (pinfunction "2_2") (pintype "passive"))
      (node (ref "S1") (pin "A2") (pinfunction "1_A2") (pintype "passive"))
      (node (ref "S2") (pin "A2") (pinfunction "1_A2") (pintype "passive"))
      (node (ref "S3") (pin "A2") (pinfunction "1_A2") (pintype "passive"))
      (node (ref "SD1") (pin "6") (pinfunction "VSS_6") (pintype "power_in"))
      (node (ref "SD1") (pin "B") (pinfunction "B_B") (pintype "passive"))
      (node (ref "SD1") (pin "MNT1") (pinfunction "S1_MNT1") (pintype "passive"))
      (node (ref "SD1") (pin "MNT2") (pinfunction "S2_MNT2") (pintype "passive"))
      (node (ref "SD1") (pin "MNT3") (pinfunction "S3_MNT3") (pintype "passive"))
      (node (ref "SD1") (pin "MNT4") (pinfunction "S4_MNT4") (pintype "passive"))
      (node (ref "U$1") (pin "2") (pinfunction "GND_2") (pintype "power_in"))
      (node (ref "U1") (pin "1") (pinfunction "GND_1") (pintype "bidirectional"))
      (node (ref "U1") (pin "15") (pinfunction "GND_15") (pintype "bidirectional"))
      (node (ref "U1") (pin "38") (pinfunction "GND_38") (pintype "bidirectional"))
      (node (ref "U1") (pin "GND") (pinfunction "GND_GND") (pintype "bidirectional"))
      (node (ref "U2") (pin "4") (pinfunction "GND_4") (pintype "passive"))
      (node (ref "USB1") (pin "P5") (pinfunction "GND_P5") (pintype "bidirectional"))
    )
    (net (code "151") (name "Net-(C42-Pad2)") (class "Default")
      (node (ref "C42") (pin "2") (pinfunction "2_2") (pintype "passive"))
      (node (ref "R13") (pin "1") (pinfunction "1_1") (pintype "passive"))
    )
    (net (code "152") (name "Net-(C43-Pad2)") (class "Default")
      (node (ref "C43") (pin "2") (pinfunction "2_2") (pintype "passive"))
      (node (ref "R14") (pin "1") (pinfunction "1_1") (pintype "passive"))
    )
    (net (code "153") (name "Net-(C44-Pad1)") (class "Default")
      (node (ref "C44") (pin "1") (pinfunction "1_1") (pintype "passive"))
      (node (ref "R16") (pin "2") (pinfunction "2_2") (pintype "passive"))
      (node (ref "R18") (pin "2") (pinfunction "2_2") (pintype "passive"))
      (node (ref "R20") (pin "1") (pinfunction "1_1") (pintype "passive"))
    )
    (net (code "154") (name "Net-(IC2-__CLK2)") (class "Default")
      (node (ref "IC2") (pin "24") (pinfunction "__CLK2_24") (pintype "input"))
      (node (ref "U$1") (pin "3") (pinfunction "FO_3") (pintype "output"))
    )
    (net (code "155") (name "Net-(IC2-__IO_77)") (class "Default")
      (node (ref "IC2") (pin "135") (pinfunction "__IO_77_135") (pintype "bidirectional"))
      (node (ref "TP6") (pin "TP") (pinfunction "TP_TP") (pintype "input"))
    )
    (net (code "156") (name "Net-(IC2-__IO_78)") (class "Default")
      (node (ref "IC2") (pin "136") (pinfunction "__IO_78_136") (pintype "bidirectional"))
      (node (ref "TP5") (pin "TP") (pinfunction "TP_TP") (pintype "input"))
    )
    (net (code "157") (name "Net-(IC2-__NSTATUS)") (class "Default")
      (node (ref "IC2") (pin "9") (pinfunction "__NSTATUS_9") (pintype "bidirectional"))
      (node (ref "R6") (pin "1") (pinfunction "1_1") (pintype "passive"))
    )
    (net (code "158") (name "Net-(IC3A-A1)") (class "Default")
      (node (ref "IC3") (pin "2") (pinfunction "A1_2") (pintype "bidirectional"))
      (node (ref "RN1") (pin "8") (pinfunction "2_8") (pintype "passive"))
    )
    (net (code "159") (name "Net-(IC3A-A2)") (class "Default")
      (node (ref "IC3") (pin "3") (pinfunction "A2_3") (pintype "bidirectional"))
      (node (ref "RN1") (pin "7") (pinfunction "2_7") (pintype "passive"))
    )
    (net (code "160") (name "Net-(IC3A-A3)") (class "Default")
      (node (ref "IC3") (pin "4") (pinfunction "A3_4") (pintype "bidirectional"))
      (node (ref "RN1") (pin "6") (pinfunction "2_6") (pintype "passive"))
    )
    (net (code "161") (name "Net-(IC3A-A4)") (class "Default")
      (node (ref "IC3") (pin "5") (pinfunction "A4_5") (pintype "bidirectional"))
      (node (ref "RN1") (pin "5") (pinfunction "2_5") (pintype "passive"))
    )
    (net (code "162") (name "Net-(IC3A-A5)") (class "Default")
      (node (ref "IC3") (pin "6") (pinfunction "A5_6") (pintype "bidirectional"))
      (node (ref "RN2") (pin "8") (pinfunction "2_8") (pintype "passive"))
    )
    (net (code "163") (name "Net-(IC3A-A6)") (class "Default")
      (node (ref "IC3") (pin "7") (pinfunction "A6_7") (pintype "bidirectional"))
      (node (ref "RN2") (pin "7") (pinfunction "2_7") (pintype "passive"))
    )
    (net (code "164") (name "Net-(IC3A-A7)") (class "Default")
      (node (ref "IC3") (pin "8") (pinfunction "A7_8") (pintype "bidirectional"))
      (node (ref "RN2") (pin "6") (pinfunction "2_6") (pintype "passive"))
    )
    (net (code "165") (name "Net-(IC3A-A8)") (class "Default")
      (node (ref "IC3") (pin "9") (pinfunction "A8_9") (pintype "bidirectional"))
      (node (ref "RN2") (pin "5") (pinfunction "2_5") (pintype "passive"))
    )
    (net (code "166") (name "Net-(IC4A-A1)") (class "Default")
      (node (ref "IC4") (pin "2") (pinfunction "A1_2") (pintype "bidirectional"))
      (node (ref "RN7") (pin "8") (pinfunction "2_8") (pintype "passive"))
    )
    (net (code "167") (name "Net-(IC4A-A2)") (class "Default")
      (node (ref "IC4") (pin "3") (pinfunction "A2_3") (pintype "bidirectional"))
      (node (ref "RN7") (pin "7") (pinfunction "2_7") (pintype "passive"))
    )
    (net (code "168") (name "Net-(IC4A-A3)") (class "Default")
      (node (ref "IC4") (pin "4") (pinfunction "A3_4") (pintype "bidirectional"))
      (node (ref "RN7") (pin "6") (pinfunction "2_6") (pintype "passive"))
    )
    (net (code "169") (name "Net-(IC4A-A4)") (class "Default")
      (node (ref "IC4") (pin "5") (pinfunction "A4_5") (pintype "bidirectional"))
      (node (ref "RN7") (pin "5") (pinfunction "2_5") (pintype "passive"))
    )
    (net (code "170") (name "Net-(IC4A-A5)") (class "Default")
      (node (ref "IC4") (pin "6") (pinfunction "A5_6") (pintype "bidirectional"))
      (node (ref "RN8") (pin "8") (pinfunction "2_8") (pintype "passive"))
    )
    (net (code "171") (name "Net-(IC4A-A6)") (class "Default")
      (node (ref "IC4") (pin "7") (pinfunction "A6_7") (pintype "bidirectional"))
      (node (ref "RN8") (pin "7") (pinfunction "2_7") (pintype "passive"))
    )
    (net (code "172") (name "Net-(IC4A-A7)") (class "Default")
      (node (ref "IC4") (pin "8") (pinfunction "A7_8") (pintype "bidirectional"))
      (node (ref "RN8") (pin "6") (pinfunction "2_6") (pintype "passive"))
    )
    (net (code "173") (name "Net-(IC4A-A8)") (class "Default")
      (node (ref "IC4") (pin "9") (pinfunction "A8_9") (pintype "bidirectional"))
      (node (ref "RN8") (pin "5") (pinfunction "2_5") (pintype "passive"))
    )
    (net (code "174") (name "Net-(IC5-BST)") (class "Default")
      (node (ref "IC5") (pin "5") (pinfunction "BST_5") (pintype "passive"))
      (node (ref "R13") (pin "2") (pinfunction "2_2") (pintype "passive"))
    )
    (net (code "175") (name "Net-(IC5-EN)") (class "Default")
      (node (ref "IC5") (pin "6") (pinfunction "EN_6") (pintype "input"))
      (node (ref "R11") (pin "1") (pinfunction "1_1") (pintype "passive"))
    )
    (net (code "176") (name "Net-(IC5-FB)") (class "Default")
      (node (ref "IC5") (pin "8") (pinfunction "FB_8") (pintype "passive"))
      (node (ref "R15") (pin "1") (pinfunction "1_1") (pintype "passive"))
    )
    (net (code "177") (name "Net-(IC5-SS)") (class "Default")
      (node (ref "C38") (pin "2") (pinfunction "2_2") (pintype "passive"))
      (node (ref "IC5") (pin "1") (pinfunction "SS_1") (pintype "passive"))
    )
    (net (code "178") (name "Net-(IC5-VCC)") (class "Default")
      (node (ref "C35") (pin "2") (pinfunction "2_2") (pintype "passive"))
      (node (ref "IC5") (pin "7") (pinfunction "VCC_7") (pintype "passive"))
    )
    (net (code "179") (name "Net-(IC6-BST)") (class "Default")
      (node (ref "IC6") (pin "5") (pinfunction "BST_5") (pintype "passive"))
      (node (ref "R14") (pin "2") (pinfunction "2_2") (pintype "passive"))
    )
    (net (code "180") (name "Net-(IC6-EN)") (class "Default")
      (node (ref "IC6") (pin "6") (pinfunction "EN_6") (pintype "input"))
      (node (ref "R12") (pin "1") (pinfunction "1_1") (pintype "passive"))
    )
    (net (code "181") (name "Net-(IC6-FB)") (class "Default")
      (node (ref "IC6") (pin "8") (pinfunction "FB_8") (pintype "passive"))
      (node (ref "R16") (pin "1") (pinfunction "1_1") (pintype "passive"))
    )
    (net (code "182") (name "Net-(IC6-SS)") (class "Default")
      (node (ref "C39") (pin "2") (pinfunction "2_2") (pintype "passive"))
      (node (ref "IC6") (pin "1") (pinfunction "SS_1") (pintype "passive"))
    )
    (net (code "183") (name "Net-(IC6-VCC)") (class "Default")
      (node (ref "C36") (pin "2") (pinfunction "2_2") (pintype "passive"))
      (node (ref "IC6") (pin "7") (pinfunction "VCC_7") (pintype "passive"))
    )
    (net (code "184") (name "Net-(IC7-DM)") (class "Default")
      (node (ref "IC7") (pin "2") (pinfunction "DM_2") (pintype "passive"))
      (node (ref "USB1") (pin "P2") (pinfunction "D-_P2") (pintype "bidirectional"))
    )
    (net (code "185") (name "Net-(IC7-DP)") (class "Default")
      (node (ref "IC7") (pin "1") (pinfunction "DP_1") (pintype "passive"))
      (node (ref "USB1") (pin "P3") (pinfunction "D+_P3") (pintype "bidirectional"))
    )
    (net (code "186") (name "Net-(IC10A-A1)") (class "Default")
      (node (ref "IC10") (pin "2") (pinfunction "A1_2") (pintype "bidirectional"))
      (node (ref "RN3") (pin "8") (pinfunction "2_8") (pintype "passive"))
    )
    (net (code "187") (name "Net-(IC10A-A2)") (class "Default")
      (node (ref "IC10") (pin "3") (pinfunction "A2_3") (pintype "bidirectional"))
      (node (ref "RN3") (pin "7") (pinfunction "2_7") (pintype "passive"))
    )
    (net (code "188") (name "Net-(IC10A-A3)") (class "Default")
      (node (ref "IC10") (pin "4") (pinfunction "A3_4") (pintype "bidirectional"))
      (node (ref "RN3") (pin "6") (pinfunction "2_6") (pintype "passive"))
    )
    (net (code "189") (name "Net-(IC10A-A4)") (class "Default")
      (node (ref "IC10") (pin "5") (pinfunction "A4_5") (pintype "bidirectional"))
      (node (ref "RN3") (pin "5") (pinfunction "2_5") (pintype "passive"))
    )
    (net (code "190") (name "Net-(IC10A-A5)") (class "Default")
      (node (ref "IC10") (pin "6") (pinfunction "A5_6") (pintype "bidirectional"))
      (node (ref "RN4") (pin "8") (pinfunction "2_8") (pintype "passive"))
    )
    (net (code "191") (name "Net-(IC10A-A6)") (class "Default")
      (node (ref "IC10") (pin "7") (pinfunction "A6_7") (pintype "bidirectional"))
      (node (ref "RN4") (pin "7") (pinfunction "2_7") (pintype "passive"))
    )
    (net (code "192") (name "Net-(IC10A-A7)") (class "Default")
      (node (ref "IC10") (pin "8") (pinfunction "A7_8") (pintype "bidirectional"))
      (node (ref "RN4") (pin "6") (pinfunction "2_6") (pintype "passive"))
    )
    (net (code "193") (name "Net-(IC10A-A8)") (class "Default")
      (node (ref "IC10") (pin "9") (pinfunction "A8_9") (pintype "bidirectional"))
      (node (ref "RN4") (pin "5") (pinfunction "2_5") (pintype "passive"))
    )
    (net (code "194") (name "Net-(IC11A-A1)") (class "Default")
      (node (ref "IC11") (pin "2") (pinfunction "A1_2") (pintype "bidirectional"))
      (node (ref "RN5") (pin "8") (pinfunction "2_8") (pintype "passive"))
    )
    (net (code "195") (name "Net-(IC11A-A2)") (class "Default")
      (node (ref "IC11") (pin "3") (pinfunction "A2_3") (pintype "bidirectional"))
      (node (ref "RN5") (pin "7") (pinfunction "2_7") (pintype "passive"))
    )
    (net (code "196") (name "Net-(IC11A-A3)") (class "Default")
      (node (ref "IC11") (pin "4") (pinfunction "A3_4") (pintype "bidirectional"))
      (node (ref "RN5") (pin "6") (pinfunction "2_6") (pintype "passive"))
    )
    (net (code "197") (name "Net-(IC11A-A4)") (class "Default")
      (node (ref "IC11") (pin "5") (pinfunction "A4_5") (pintype "bidirectional"))
      (node (ref "RN5") (pin "5") (pinfunction "2_5") (pintype "passive"))
    )
    (net (code "198") (name "Net-(IC11A-A5)") (class "Default")
      (node (ref "IC11") (pin "6") (pinfunction "A5_6") (pintype "bidirectional"))
      (node (ref "RN6") (pin "8") (pinfunction "2_8") (pintype "passive"))
    )
    (net (code "199") (name "Net-(IC11A-A6)") (class "Default")
      (node (ref "IC11") (pin "7") (pinfunction "A6_7") (pintype "bidirectional"))
      (node (ref "RN6") (pin "7") (pinfunction "2_7") (pintype "passive"))
    )
    (net (code "200") (name "Net-(IC11A-A7)") (class "Default")
      (node (ref "IC11") (pin "8") (pinfunction "A7_8") (pintype "bidirectional"))
      (node (ref "RN6") (pin "6") (pinfunction "2_6") (pintype "passive"))
    )
    (net (code "201") (name "Net-(IC11A-A8)") (class "Default")
      (node (ref "IC11") (pin "9") (pinfunction "A8_9") (pintype "bidirectional"))
      (node (ref "RN6") (pin "5") (pinfunction "2_5") (pintype "passive"))
    )
    (net (code "202") (name "Net-(LED1-PadC)") (class "Default")
      (node (ref "LED1") (pin "C") (pinfunction "C_C") (pintype "passive"))
      (node (ref "R21") (pin "1") (pinfunction "1_1") (pintype "passive"))
    )
    (net (code "203") (name "Net-(LED2-PadC)") (class "Default")
      (node (ref "LED2") (pin "C") (pinfunction "C_C") (pintype "passive"))
      (node (ref "R22") (pin "1") (pinfunction "1_1") (pintype "passive"))
    )
    (net (code "204") (name "Net-(LED3-PadC)") (class "Default")
      (node (ref "LED3") (pin "C") (pinfunction "C_C") (pintype "passive"))
      (node (ref "R23") (pin "1") (pinfunction "1_1") (pintype "passive"))
    )
    (net (code "205") (name "Net-(R15-Pad2)") (class "Default")
      (node (ref "R15") (pin "2") (pinfunction "2_2") (pintype "passive"))
      (node (ref "R17") (pin "2") (pinfunction "2_2") (pintype "passive"))
      (node (ref "R19") (pin "1") (pinfunction "1_1") (pintype "passive"))
    )
    (net (code "206") (name "unconnected-(CONN1-BUSACK-PadA26)") (class "Default")
      (node (ref "CONN1") (pin "A26") (pinfunction "BUSACK_A26") (pintype "bidirectional"))
    )
    (net (code "207") (name "unconnected-(CONN1-BUSREQ-PadA19)") (class "Default")
      (node (ref "CONN1") (pin "A19") (pinfunction "BUSREQ_A19") (pintype "bidirectional"))
    )
    (net (code "208") (name "unconnected-(CONN1-HALT-PadB15)") (class "Default")
      (node (ref "CONN1") (pin "B15") (pinfunction "HALT_B15") (pintype "bidirectional"))
    )
    (net (code "209") (name "unconnected-(CONN1-IORQULA-PadA13)") (class "Default")
      (node (ref "CONN1") (pin "A13") (pinfunction "IORQULA_A13") (pintype "bidirectional"))
    )
    (net (code "210") (name "unconnected-(CONN1-NC-PadB28)") (class "Default")
      (node (ref "CONN1") (pin "B28") (pinfunction "NC_B28") (pintype "bidirectional"))
    )
    (net (code "211") (name "unconnected-(CONN1-NC3-PadB4)") (class "Default")
      (node (ref "CONN1") (pin "B4") (pinfunction "NC3_B4") (pintype "passive"))
    )
    (net (code "212") (name "unconnected-(CONN1-NMI-PadB14)") (class "Default")
      (node (ref "CONN1") (pin "B14") (pinfunction "NMI_B14") (pintype "bidirectional"))
    )
    (net (code "213") (name "unconnected-(CONN1-U-PadA18)") (class "Default")
      (node (ref "CONN1") (pin "A18") (pinfunction "U_A18") (pintype "bidirectional"))
    )
    (net (code "214") (name "unconnected-(CONN1-V-PadA17)") (class "Default")
      (node (ref "CONN1") (pin "A17") (pinfunction "V_A17") (pintype "bidirectional"))
    )
    (net (code "215") (name "unconnected-(CONN1-VIDEO-PadA15)") (class "Default")
      (node (ref "CONN1") (pin "A15") (pinfunction "VIDEO_A15") (pintype "bidirectional"))
    )
    (net (code "216") (name "unconnected-(CONN1-WAIT-PadB21)") (class "Default")
      (node (ref "CONN1") (pin "B21") (pinfunction "WAIT_B21") (pintype "bidirectional"))
    )
    (net (code "217") (name "unconnected-(CONN1-YL-PadA16)") (class "Default")
      (node (ref "CONN1") (pin "A16") (pinfunction "YL_A16") (pintype "bidirectional"))
    )
    (net (code "218") (name "unconnected-(CONN2-Pad6)") (class "Default")
      (node (ref "CONN2") (pin "6") (pinfunction "6_6") (pintype "passive"))
    )
    (net (code "219") (name "unconnected-(CONN2-Pad7)") (class "Default")
      (node (ref "CONN2") (pin "7") (pinfunction "7_7") (pintype "passive"))
    )
    (net (code "220") (name "unconnected-(CONN2-Pad8)") (class "Default")
      (node (ref "CONN2") (pin "8") (pinfunction "8_8") (pintype "passive"))
    )
    (net (code "221") (name "unconnected-(IC2-__CLK3-Pad25)") (class "Default")
      (node (ref "IC2") (pin "25") (pinfunction "__CLK3_25") (pintype "input"))
    )
    (net (code "222") (name "unconnected-(IC2-__CLK4-Pad91)") (class "Default")
      (node (ref "IC2") (pin "91") (pinfunction "__CLK4_91") (pintype "input"))
    )
    (net (code "223") (name "unconnected-(IC2-__CLK5-Pad90)") (class "Default")
      (node (ref "IC2") (pin "90") (pinfunction "__CLK5_90") (pintype "input"))
    )
    (net (code "224") (name "unconnected-(IC2-__CLK6-Pad89)") (class "Default")
      (node (ref "IC2") (pin "89") (pinfunction "__CLK6_89") (pintype "input"))
    )
    (net (code "225") (name "unconnected-(IC2-__CLK7-Pad88)") (class "Default")
      (node (ref "IC2") (pin "88") (pinfunction "__CLK7_88") (pintype "input"))
    )
    (net (code "226") (name "unconnected-(IC2-__IO_76-Pad133)") (class "Default")
      (node (ref "IC2") (pin "133") (pinfunction "__IO_76_133") (pintype "bidirectional"))
    )
    (net (code "227") (name "unconnected-(IC7-RTS-Pad4)") (class "Default")
      (node (ref "IC7") (pin "4") (pinfunction "RTS_4") (pintype "output"))
    )
    (net (code "228") (name "unconnected-(IC9A-DQ8-Pad42)") (class "Default")
      (node (ref "IC9") (pin "42") (pinfunction "DQ8_42") (pintype "tri_state"))
    )
    (net (code "229") (name "unconnected-(IC9A-DQ9-Pad44)") (class "Default")
      (node (ref "IC9") (pin "44") (pinfunction "DQ9_44") (pintype "tri_state"))
    )
    (net (code "230") (name "unconnected-(IC9A-DQ10-Pad45)") (class "Default")
      (node (ref "IC9") (pin "45") (pinfunction "DQ10_45") (pintype "tri_state"))
    )
    (net (code "231") (name "unconnected-(IC9A-DQ11-Pad47)") (class "Default")
      (node (ref "IC9") (pin "47") (pinfunction "DQ11_47") (pintype "tri_state"))
    )
    (net (code "232") (name "unconnected-(IC9A-DQ12-Pad48)") (class "Default")
      (node (ref "IC9") (pin "48") (pinfunction "DQ12_48") (pintype "tri_state"))
    )
    (net (code "233") (name "unconnected-(IC9A-DQ13-Pad50)") (class "Default")
      (node (ref "IC9") (pin "50") (pinfunction "DQ13_50") (pintype "tri_state"))
    )
    (net (code "234") (name "unconnected-(IC9A-DQ14-Pad51)") (class "Default")
      (node (ref "IC9") (pin "51") (pinfunction "DQ14_51") (pintype "tri_state"))
    )
    (net (code "235") (name "unconnected-(IC9A-DQ15-Pad53)") (class "Default")
      (node (ref "IC9") (pin "53") (pinfunction "DQ15_53") (pintype "tri_state"))
    )
    (net (code "236") (name "unconnected-(IC9A-DQML-Pad15)") (class "Default")
      (node (ref "IC9") (pin "15") (pinfunction "DQML_15") (pintype "input"))
    )
    (net (code "237") (name "unconnected-(IC9A-NC-Pad40)") (class "Default")
      (node (ref "IC9") (pin "40") (pinfunction "NC_40") (pintype "no_connect"))
    )
    (net (code "238") (name "unconnected-(U1-IO2-Pad24)") (class "Default")
      (node (ref "U1") (pin "24") (pinfunction "IO2_24") (pintype "bidirectional"))
    )
    (net (code "239") (name "unconnected-(U1-IO4-Pad26)") (class "Default")
      (node (ref "U1") (pin "26") (pinfunction "IO4_26") (pintype "bidirectional"))
    )
    (net (code "240") (name "unconnected-(U1-IO12-Pad14)") (class "Default")
      (node (ref "U1") (pin "14") (pinfunction "IO12_14") (pintype "bidirectional"))
    )
    (net (code "241") (name "unconnected-(U1-IO13-Pad16)") (class "Default")
      (node (ref "U1") (pin "16") (pinfunction "IO13_16") (pintype "bidirectional"))
    )
    (net (code "242") (name "unconnected-(U1-IO16-Pad27)") (class "Default")
      (node (ref "U1") (pin "27") (pinfunction "IO16_27") (pintype "bidirectional"))
    )
    (net (code "243") (name "unconnected-(U1-IO17-Pad28)") (class "Default")
      (node (ref "U1") (pin "28") (pinfunction "IO17_28") (pintype "bidirectional"))
    )
    (net (code "244") (name "unconnected-(U1-IO35-Pad7)") (class "Default")
      (node (ref "U1") (pin "7") (pinfunction "IO35_7") (pintype "input"))
    )
    (net (code "245") (name "unconnected-(U1-NC-Pad32)") (class "Default")
      (node (ref "U1") (pin "32") (pinfunction "NC_32") (pintype "bidirectional"))
    )
    (net (code "246") (name "unconnected-(U1-SENSOR_VN-Pad5)") (class "Default")
      (node (ref "U1") (pin "5") (pinfunction "SENSOR_VN_5") (pintype "input"))
    )
    (net (code "247") (name "unconnected-(U1-SENSOR_VP-Pad4)") (class "Default")
      (node (ref "U1") (pin "4") (pinfunction "SENSOR_VP_4") (pintype "input"))
    )
    (net (code "248") (name "unconnected-(USB1B-USBID-PadP4)") (class "Default")
      (node (ref "USB1") (pin "P4") (pinfunction "USBID_P4") (pintype "bidirectional"))
    )
    (net (code "249") (name "unconnected-(USB1B-VUSB-PadP1)") (class "Default")
      (node (ref "USB1") (pin "P1") (pinfunction "VUSB_P1") (pintype "bidirectional"))
    )
  )
)
